# Allwinner_V3s_Dev-board.net
KiCad netlist of a schematic drawn in EAGLE
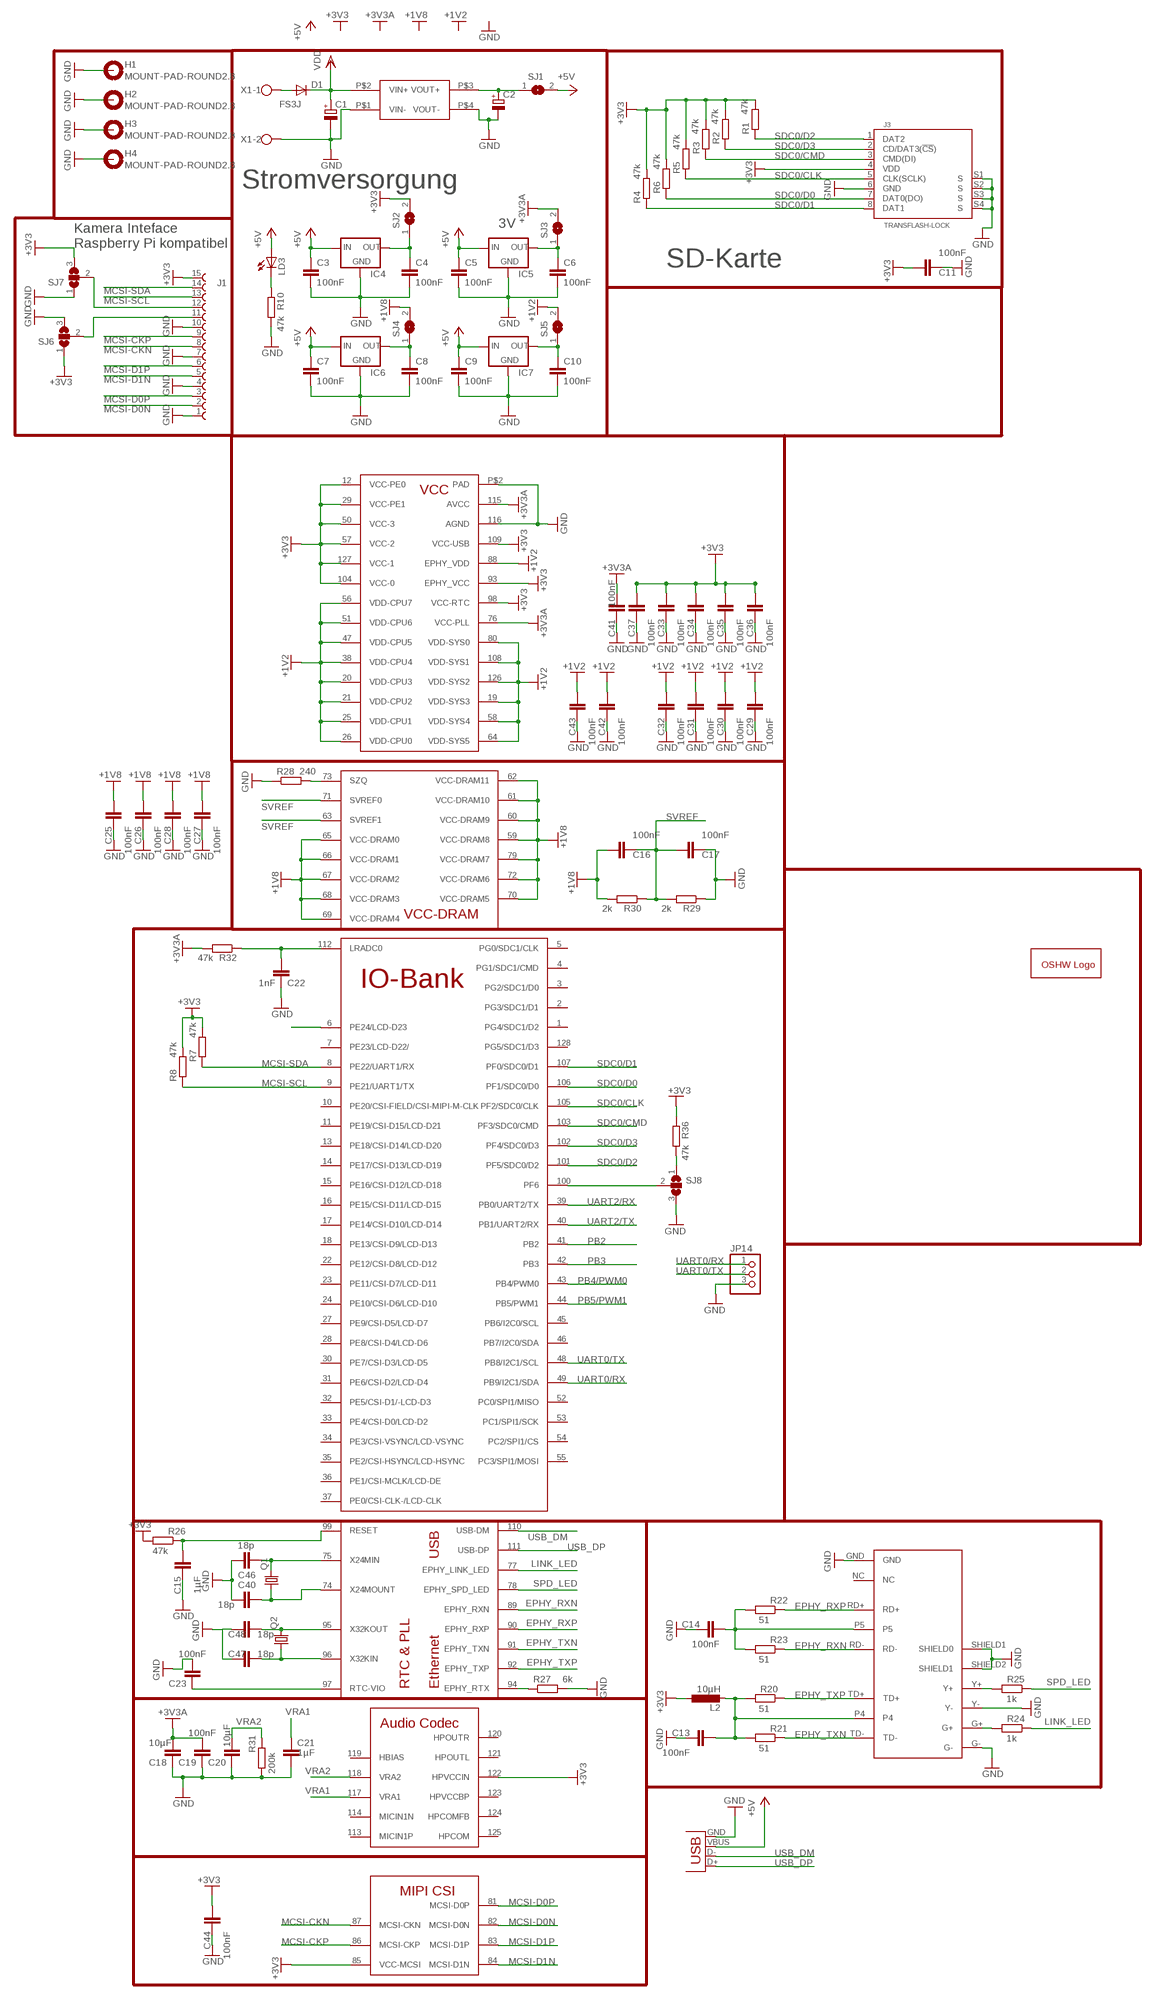
[diagram p0: schematic, sheet 1, part 1 of 2]
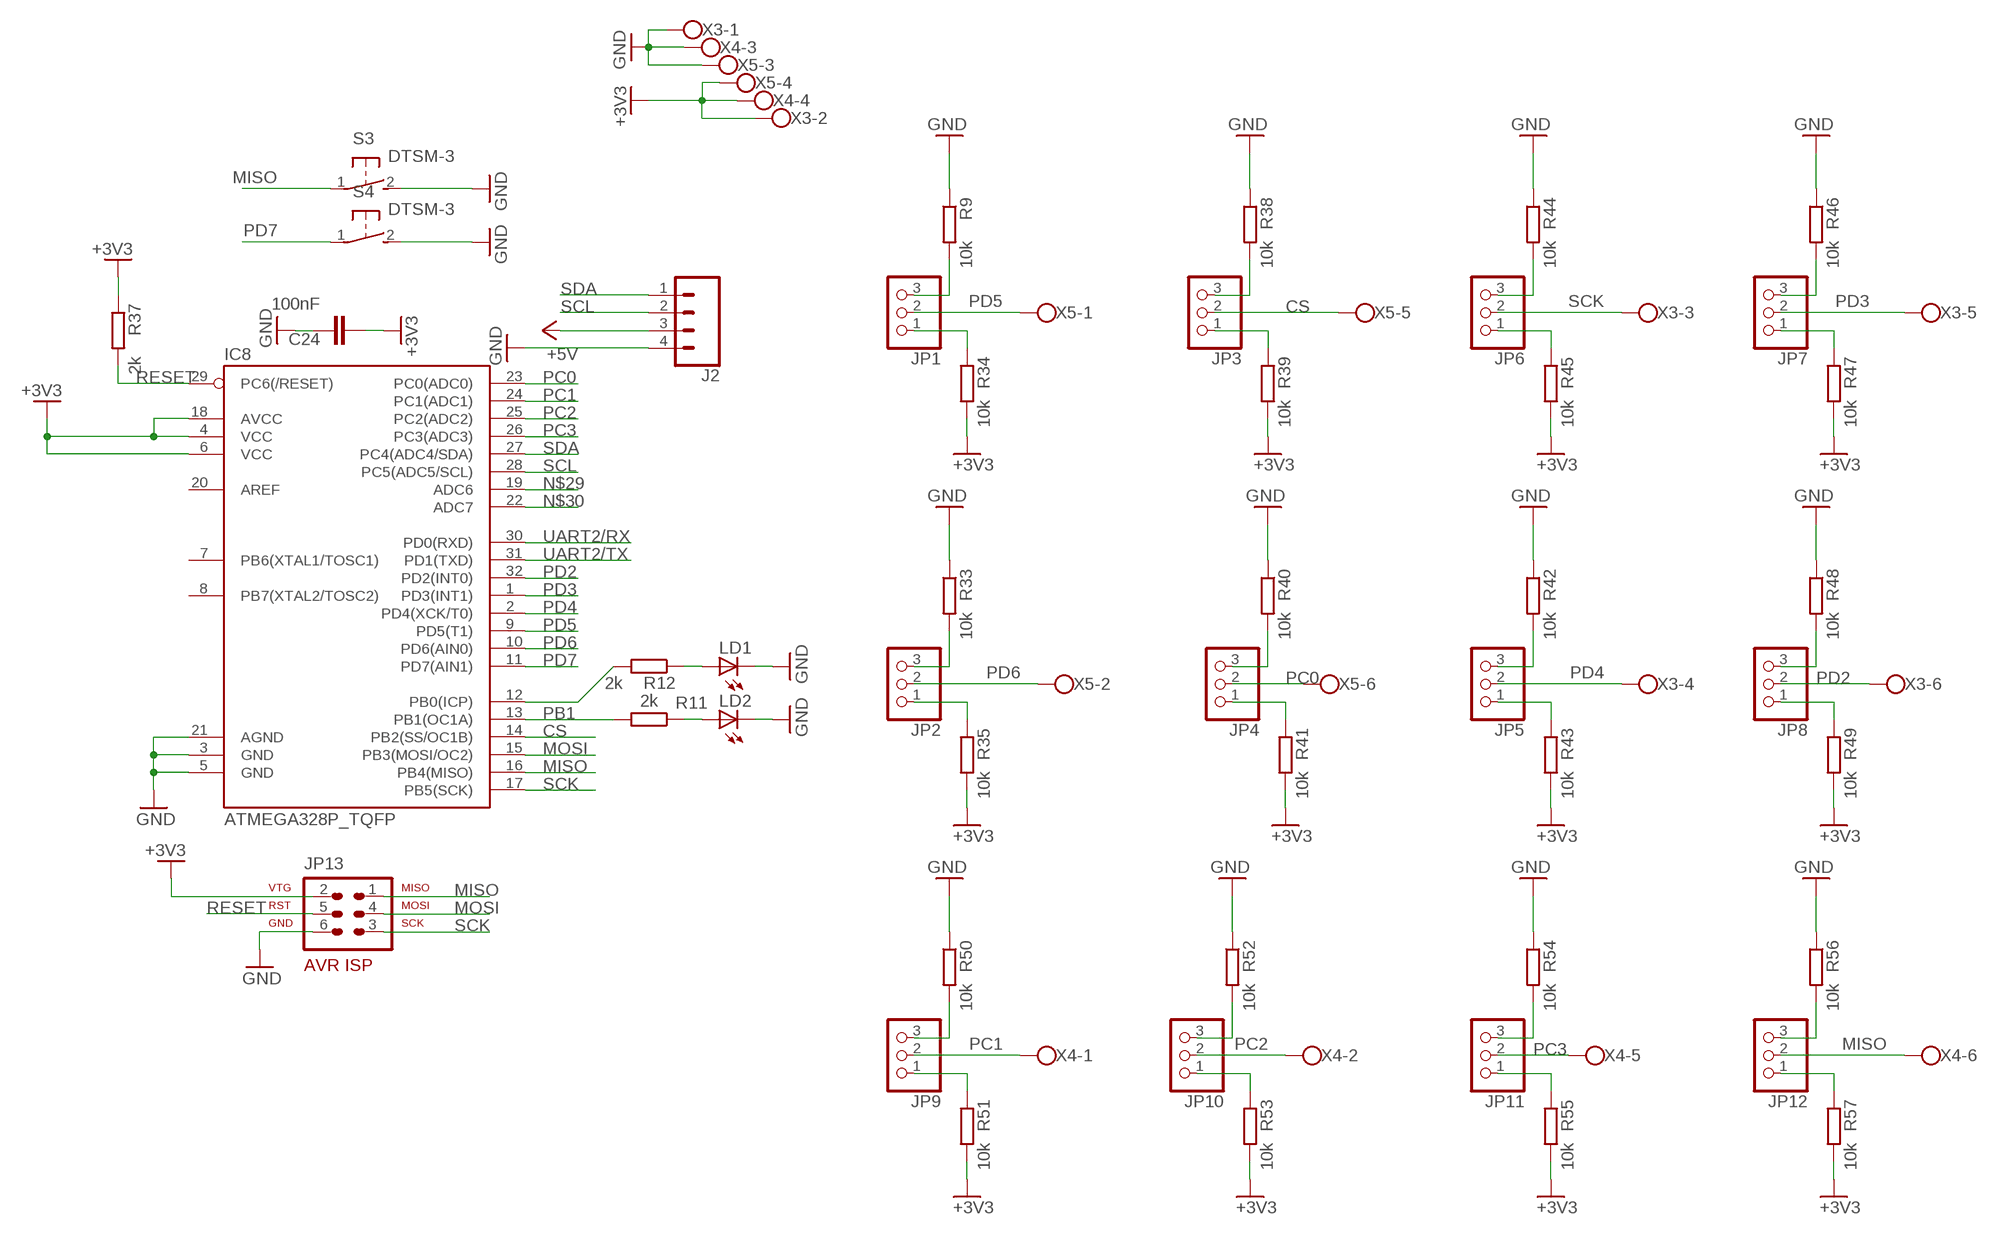
[diagram p1: schematic, sheet 1, part 2 of 2]

(export (version "E")
  (design (tool "Eeschema 10.0.6"))
  (components
    (comp (ref "C1")
      (value "CPOL-EU153CLV-0807")
      (footprint "eagle-import:153CLV-0807")
      (libsource (lib "eagle-import") (part "CPOL-EU153CLV-0807"))
    )
    (comp (ref "C2")
      (value "CPOL-EU153CLV-0807")
      (footprint "eagle-import:153CLV-0807")
      (libsource (lib "eagle-import") (part "CPOL-EU153CLV-0807"))
    )
    (comp (ref "C3")
      (value "100nF")
      (footprint "eagle-import:C0805")
      (libsource (lib "eagle-import") (part "C-EUC0805"))
    )
    (comp (ref "C4")
      (value "100nF")
      (footprint "eagle-import:C0805")
      (libsource (lib "eagle-import") (part "C-EUC0805"))
    )
    (comp (ref "C5")
      (value "100nF")
      (footprint "eagle-import:C0805")
      (libsource (lib "eagle-import") (part "C-EUC0805"))
    )
    (comp (ref "C6")
      (value "100nF")
      (footprint "eagle-import:C0805")
      (libsource (lib "eagle-import") (part "C-EUC0805"))
    )
    (comp (ref "C7")
      (value "100nF")
      (footprint "eagle-import:C0805")
      (libsource (lib "eagle-import") (part "C-EUC0805"))
    )
    (comp (ref "C8")
      (value "100nF")
      (footprint "eagle-import:C0805")
      (libsource (lib "eagle-import") (part "C-EUC0805"))
    )
    (comp (ref "C9")
      (value "100nF")
      (footprint "eagle-import:C0805")
      (libsource (lib "eagle-import") (part "C-EUC0805"))
    )
    (comp (ref "C10")
      (value "100nF")
      (footprint "eagle-import:C0805")
      (libsource (lib "eagle-import") (part "C-EUC0805"))
    )
    (comp (ref "C11")
      (value "100nF")
      (footprint "eagle-import:C0805")
      (libsource (lib "eagle-import") (part "C-EUC0805"))
    )
    (comp (ref "C13")
      (value "100nF")
      (footprint "eagle-import:C0805")
      (libsource (lib "eagle-import") (part "C-EUC0805"))
    )
    (comp (ref "C14")
      (value "100nF")
      (footprint "eagle-import:C0805")
      (libsource (lib "eagle-import") (part "C-EUC0805"))
    )
    (comp (ref "C15")
      (value "1µF")
      (footprint "eagle-import:C0805")
      (libsource (lib "eagle-import") (part "C-EUC0805"))
    )
    (comp (ref "C16")
      (value "100nF")
      (footprint "eagle-import:C0805")
      (libsource (lib "eagle-import") (part "C-EUC0805"))
    )
    (comp (ref "C17")
      (value "100nF")
      (footprint "eagle-import:C0805")
      (libsource (lib "eagle-import") (part "C-EUC0805"))
    )
    (comp (ref "C18")
      (value "10µF")
      (footprint "eagle-import:C0805")
      (libsource (lib "eagle-import") (part "C-EUC0805"))
    )
    (comp (ref "C19")
      (value "100nF")
      (footprint "eagle-import:C0805")
      (libsource (lib "eagle-import") (part "C-EUC0805"))
    )
    (comp (ref "C20")
      (value "10µF")
      (footprint "eagle-import:C0805")
      (libsource (lib "eagle-import") (part "C-EUC0805"))
    )
    (comp (ref "C21")
      (value "1µF")
      (footprint "eagle-import:C0805")
      (libsource (lib "eagle-import") (part "C-EUC0805"))
    )
    (comp (ref "C22")
      (value "1nF")
      (footprint "eagle-import:C0805")
      (libsource (lib "eagle-import") (part "C-EUC0805"))
    )
    (comp (ref "C23")
      (value "100nF")
      (footprint "eagle-import:C0805")
      (libsource (lib "eagle-import") (part "C-EUC0805"))
    )
    (comp (ref "C24")
      (value "100nF")
      (footprint "eagle-import:C0805")
      (libsource (lib "eagle-import") (part "C-EUC0805"))
    )
    (comp (ref "C25")
      (value "100nF")
      (footprint "eagle-import:C0805")
      (libsource (lib "eagle-import") (part "C-EUC0805"))
    )
    (comp (ref "C26")
      (value "100nF")
      (footprint "eagle-import:C0805")
      (libsource (lib "eagle-import") (part "C-EUC0805"))
    )
    (comp (ref "C27")
      (value "100nF")
      (footprint "eagle-import:C0805")
      (libsource (lib "eagle-import") (part "C-EUC0805"))
    )
    (comp (ref "C28")
      (value "100nF")
      (footprint "eagle-import:C0805")
      (libsource (lib "eagle-import") (part "C-EUC0805"))
    )
    (comp (ref "C29")
      (value "100nF")
      (footprint "eagle-import:C0805")
      (libsource (lib "eagle-import") (part "C-EUC0805"))
    )
    (comp (ref "C30")
      (value "100nF")
      (footprint "eagle-import:C0805")
      (libsource (lib "eagle-import") (part "C-EUC0805"))
    )
    (comp (ref "C31")
      (value "100nF")
      (footprint "eagle-import:C0805")
      (libsource (lib "eagle-import") (part "C-EUC0805"))
    )
    (comp (ref "C32")
      (value "100nF")
      (footprint "eagle-import:C0805")
      (libsource (lib "eagle-import") (part "C-EUC0805"))
    )
    (comp (ref "C33")
      (value "100nF")
      (footprint "eagle-import:C0805")
      (libsource (lib "eagle-import") (part "C-EUC0805"))
    )
    (comp (ref "C34")
      (value "100nF")
      (footprint "eagle-import:C0805")
      (libsource (lib "eagle-import") (part "C-EUC0805"))
    )
    (comp (ref "C35")
      (value "100nF")
      (footprint "eagle-import:C0805")
      (libsource (lib "eagle-import") (part "C-EUC0805"))
    )
    (comp (ref "C36")
      (value "100nF")
      (footprint "eagle-import:C0805")
      (libsource (lib "eagle-import") (part "C-EUC0805"))
    )
    (comp (ref "C37")
      (value "100nF")
      (footprint "eagle-import:C0805")
      (libsource (lib "eagle-import") (part "C-EUC0805"))
    )
    (comp (ref "C40")
      (value "18p")
      (footprint "eagle-import:C0805")
      (libsource (lib "eagle-import") (part "C-EUC0805"))
    )
    (comp (ref "C41")
      (value "100nF")
      (footprint "eagle-import:C0805")
      (libsource (lib "eagle-import") (part "C-EUC0805"))
    )
    (comp (ref "C42")
      (value "100nF")
      (footprint "eagle-import:C0805")
      (libsource (lib "eagle-import") (part "C-EUC0805"))
    )
    (comp (ref "C43")
      (value "100nF")
      (footprint "eagle-import:C0805")
      (libsource (lib "eagle-import") (part "C-EUC0805"))
    )
    (comp (ref "C44")
      (value "100nF")
      (footprint "eagle-import:C0805")
      (libsource (lib "eagle-import") (part "C-EUC0805"))
    )
    (comp (ref "C46")
      (value "18p")
      (footprint "eagle-import:C0805")
      (libsource (lib "eagle-import") (part "C-EUC0805"))
    )
    (comp (ref "C47")
      (value "18p")
      (footprint "eagle-import:C0805")
      (libsource (lib "eagle-import") (part "C-EUC0805"))
    )
    (comp (ref "C48")
      (value "18p")
      (footprint "eagle-import:C0805")
      (libsource (lib "eagle-import") (part "C-EUC0805"))
    )
    (comp (ref "D1")
      (value "FS3J")
      (footprint "eagle-import:SMC")
      (libsource (lib "eagle-import") (part "DIODE-SMC"))
    )
    (comp (ref "GOLD_ORB_SM2")
      (value "OSHWLOGOLOGO8MM")
      (footprint "eagle-import:OSHW_8MM")
      (libsource (lib "eagle-import") (part "OSHWLOGOLOGO8MM"))
    )
    (comp (ref "H1")
      (value "MOUNT-PAD-ROUND2.8")
      (footprint "eagle-import:2,8-PAD")
      (libsource (lib "eagle-import") (part "MOUNT-PAD-ROUND2.8"))
    )
    (comp (ref "H2")
      (value "MOUNT-PAD-ROUND2.8")
      (footprint "eagle-import:2,8-PAD")
      (libsource (lib "eagle-import") (part "MOUNT-PAD-ROUND2.8"))
    )
    (comp (ref "H3")
      (value "MOUNT-PAD-ROUND2.8")
      (footprint "eagle-import:2,8-PAD")
      (libsource (lib "eagle-import") (part "MOUNT-PAD-ROUND2.8"))
    )
    (comp (ref "H4")
      (value "MOUNT-PAD-ROUND2.8")
      (footprint "eagle-import:2,8-PAD")
      (libsource (lib "eagle-import") (part "MOUNT-PAD-ROUND2.8"))
    )
    (comp (ref "IC1")
      (value "V3S")
      (footprint "eagle-import:QFP-128")
      (libsource (lib "eagle-import") (part "V3S"))
    )
    (comp (ref "IC4")
      (value "LM1117")
      (footprint "eagle-import:SOT223")
      (libsource (lib "eagle-import") (part "LM1117"))
    )
    (comp (ref "IC5")
      (value "LM1117")
      (footprint "eagle-import:SOT223")
      (libsource (lib "eagle-import") (part "LM1117"))
    )
    (comp (ref "IC6")
      (value "LM1117")
      (footprint "eagle-import:SOT223")
      (libsource (lib "eagle-import") (part "LM1117"))
    )
    (comp (ref "IC7")
      (value "LM1117")
      (footprint "eagle-import:SOT223")
      (libsource (lib "eagle-import") (part "LM1117"))
    )
    (comp (ref "IC8")
      (value "ATMEGA328P_TQFP")
      (footprint "eagle-import:TQFP32-08")
      (libsource (lib "eagle-import") (part "ATMEGA328P_TQFP"))
    )
    (comp (ref "J1")
      (value "68611514122")
      (footprint "eagle-import:68611514122")
      (libsource (lib "eagle-import") (part "68611514122"))
    )
    (comp (ref "J2")
      (value "CONN_04SMD_LONG")
      (footprint "eagle-import:1X04_SMD_LONG")
      (libsource (lib "eagle-import") (part "CONN_04SMD_LONG"))
    )
    (comp (ref "J3")
      (value "TRANSFLASH-LOCK")
      (footprint "eagle-import:TRANSFLASH-LOCK-SOCK")
      (libsource (lib "eagle-import") (part "TRANSFLASH-LOCK"))
    )
    (comp (ref "JP1")
      (value "PINHD-1X3")
      (footprint "eagle-import:1X03")
      (libsource (lib "eagle-import") (part "PINHD-1X3"))
    )
    (comp (ref "JP2")
      (value "PINHD-1X3")
      (footprint "eagle-import:1X03")
      (libsource (lib "eagle-import") (part "PINHD-1X3"))
    )
    (comp (ref "JP3")
      (value "PINHD-1X3")
      (footprint "eagle-import:1X03")
      (libsource (lib "eagle-import") (part "PINHD-1X3"))
    )
    (comp (ref "JP4")
      (value "PINHD-1X3")
      (footprint "eagle-import:1X03")
      (libsource (lib "eagle-import") (part "PINHD-1X3"))
    )
    (comp (ref "JP5")
      (value "PINHD-1X3")
      (footprint "eagle-import:1X03")
      (libsource (lib "eagle-import") (part "PINHD-1X3"))
    )
    (comp (ref "JP6")
      (value "PINHD-1X3")
      (footprint "eagle-import:1X03")
      (libsource (lib "eagle-import") (part "PINHD-1X3"))
    )
    (comp (ref "JP7")
      (value "PINHD-1X3")
      (footprint "eagle-import:1X03")
      (libsource (lib "eagle-import") (part "PINHD-1X3"))
    )
    (comp (ref "JP8")
      (value "PINHD-1X3")
      (footprint "eagle-import:1X03")
      (libsource (lib "eagle-import") (part "PINHD-1X3"))
    )
    (comp (ref "JP9")
      (value "PINHD-1X3")
      (footprint "eagle-import:1X03")
      (libsource (lib "eagle-import") (part "PINHD-1X3"))
    )
    (comp (ref "JP10")
      (value "PINHD-1X3")
      (footprint "eagle-import:1X03")
      (libsource (lib "eagle-import") (part "PINHD-1X3"))
    )
    (comp (ref "JP11")
      (value "PINHD-1X3")
      (footprint "eagle-import:1X03")
      (libsource (lib "eagle-import") (part "PINHD-1X3"))
    )
    (comp (ref "JP12")
      (value "PINHD-1X3")
      (footprint "eagle-import:1X03")
      (libsource (lib "eagle-import") (part "PINHD-1X3"))
    )
    (comp (ref "JP13")
      (value "AVR-ISP-6")
      (footprint "eagle-import:AVR-ISP-6")
      (libsource (lib "eagle-import") (part "AVR-ISP-6"))
    )
    (comp (ref "JP14")
      (value "PINHD-1X3")
      (footprint "eagle-import:1X03")
      (libsource (lib "eagle-import") (part "PINHD-1X3"))
    )
    (comp (ref "L2")
      (value "10µH")
      (footprint "eagle-import:L0805")
      (libsource (lib "eagle-import") (part "L-EUL0805"))
    )
    (comp (ref "LD1")
      (value "LEDSMT1206")
      (footprint "eagle-import:1206")
      (libsource (lib "eagle-import") (part "LEDSMT1206"))
    )
    (comp (ref "LD2")
      (value "LEDSMT1206")
      (footprint "eagle-import:1206")
      (libsource (lib "eagle-import") (part "LEDSMT1206"))
    )
    (comp (ref "LD3")
      (value "LEDSMT1206")
      (footprint "eagle-import:1206")
      (libsource (lib "eagle-import") (part "LEDSMT1206"))
    )
    (comp (ref "M1")
      (value "MP1584-MINI")
      (footprint "eagle-import:MINI-DC-BRICK")
      (libsource (lib "eagle-import") (part "MP1584-MINI"))
    )
    (comp (ref "Q1")
      (value "CRYSTALHC49S")
      (footprint "eagle-import:HC49_S")
      (libsource (lib "eagle-import") (part "CRYSTALHC49S"))
    )
    (comp (ref "Q2")
      (value "CRYSTALTC26H")
      (footprint "eagle-import:TC26H")
      (libsource (lib "eagle-import") (part "CRYSTALTC26H"))
    )
    (comp (ref "R1")
      (value "47k")
      (footprint "eagle-import:R0805")
      (libsource (lib "eagle-import") (part "R-EU_R0805"))
    )
    (comp (ref "R2")
      (value "47k")
      (footprint "eagle-import:R0805")
      (libsource (lib "eagle-import") (part "R-EU_R0805"))
    )
    (comp (ref "R3")
      (value "47k")
      (footprint "eagle-import:R0805")
      (libsource (lib "eagle-import") (part "R-EU_R0805"))
    )
    (comp (ref "R4")
      (value "47k")
      (footprint "eagle-import:R0805")
      (libsource (lib "eagle-import") (part "R-EU_R0805"))
    )
    (comp (ref "R5")
      (value "47k")
      (footprint "eagle-import:R0805")
      (libsource (lib "eagle-import") (part "R-EU_R0805"))
    )
    (comp (ref "R6")
      (value "47k")
      (footprint "eagle-import:R0805")
      (libsource (lib "eagle-import") (part "R-EU_R0805"))
    )
    (comp (ref "R7")
      (value "47k")
      (footprint "eagle-import:R0805")
      (libsource (lib "eagle-import") (part "R-EU_R0805"))
    )
    (comp (ref "R8")
      (value "47k")
      (footprint "eagle-import:R0805")
      (libsource (lib "eagle-import") (part "R-EU_R0805"))
    )
    (comp (ref "R9")
      (value "10k")
      (footprint "eagle-import:R0805")
      (libsource (lib "eagle-import") (part "R-EU_R0805"))
    )
    (comp (ref "R10")
      (value "47k")
      (footprint "eagle-import:R0805")
      (libsource (lib "eagle-import") (part "R-EU_R0805"))
    )
    (comp (ref "R11")
      (value "2k")
      (footprint "eagle-import:R0805")
      (libsource (lib "eagle-import") (part "R-EU_R0805"))
    )
    (comp (ref "R12")
      (value "2k")
      (footprint "eagle-import:R0805")
      (libsource (lib "eagle-import") (part "R-EU_R0805"))
    )
    (comp (ref "R20")
      (value "51")
      (footprint "eagle-import:R0805")
      (libsource (lib "eagle-import") (part "R-EU_R0805"))
    )
    (comp (ref "R21")
      (value "51")
      (footprint "eagle-import:R0805")
      (libsource (lib "eagle-import") (part "R-EU_R0805"))
    )
    (comp (ref "R22")
      (value "51")
      (footprint "eagle-import:R0805")
      (libsource (lib "eagle-import") (part "R-EU_R0805"))
    )
    (comp (ref "R23")
      (value "51")
      (footprint "eagle-import:R0805")
      (libsource (lib "eagle-import") (part "R-EU_R0805"))
    )
    (comp (ref "R24")
      (value "1k")
      (footprint "eagle-import:R0805")
      (libsource (lib "eagle-import") (part "R-EU_R0805"))
    )
    (comp (ref "R25")
      (value "1k")
      (footprint "eagle-import:R0805")
      (libsource (lib "eagle-import") (part "R-EU_R0805"))
    )
    (comp (ref "R26")
      (value "47k")
      (footprint "eagle-import:R0805")
      (libsource (lib "eagle-import") (part "R-EU_R0805"))
    )
    (comp (ref "R27")
      (value "6k")
      (footprint "eagle-import:R0805")
      (libsource (lib "eagle-import") (part "R-EU_R0805"))
    )
    (comp (ref "R28")
      (value "240")
      (footprint "eagle-import:R0805")
      (libsource (lib "eagle-import") (part "R-EU_R0805"))
    )
    (comp (ref "R29")
      (value "2k")
      (footprint "eagle-import:R0805")
      (libsource (lib "eagle-import") (part "R-EU_R0805"))
    )
    (comp (ref "R30")
      (value "2k")
      (footprint "eagle-import:R0805")
      (libsource (lib "eagle-import") (part "R-EU_R0805"))
    )
    (comp (ref "R31")
      (value "200k")
      (footprint "eagle-import:R0805")
      (libsource (lib "eagle-import") (part "R-EU_R0805"))
    )
    (comp (ref "R32")
      (value "47k")
      (footprint "eagle-import:R0805")
      (libsource (lib "eagle-import") (part "R-EU_R0805"))
    )
    (comp (ref "R33")
      (value "10k")
      (footprint "eagle-import:R0805")
      (libsource (lib "eagle-import") (part "R-EU_R0805"))
    )
    (comp (ref "R34")
      (value "10k")
      (footprint "eagle-import:R0805")
      (libsource (lib "eagle-import") (part "R-EU_R0805"))
    )
    (comp (ref "R35")
      (value "10k")
      (footprint "eagle-import:R0805")
      (libsource (lib "eagle-import") (part "R-EU_R0805"))
    )
    (comp (ref "R36")
      (value "47k")
      (footprint "eagle-import:R0805")
      (libsource (lib "eagle-import") (part "R-EU_R0805"))
    )
    (comp (ref "R37")
      (value "2k")
      (footprint "eagle-import:R0805")
      (libsource (lib "eagle-import") (part "R-EU_R0805"))
    )
    (comp (ref "R38")
      (value "10k")
      (footprint "eagle-import:R0805")
      (libsource (lib "eagle-import") (part "R-EU_R0805"))
    )
    (comp (ref "R39")
      (value "10k")
      (footprint "eagle-import:R0805")
      (libsource (lib "eagle-import") (part "R-EU_R0805"))
    )
    (comp (ref "R40")
      (value "10k")
      (footprint "eagle-import:R0805")
      (libsource (lib "eagle-import") (part "R-EU_R0805"))
    )
    (comp (ref "R41")
      (value "10k")
      (footprint "eagle-import:R0805")
      (libsource (lib "eagle-import") (part "R-EU_R0805"))
    )
    (comp (ref "R42")
      (value "10k")
      (footprint "eagle-import:R0805")
      (libsource (lib "eagle-import") (part "R-EU_R0805"))
    )
    (comp (ref "R43")
      (value "10k")
      (footprint "eagle-import:R0805")
      (libsource (lib "eagle-import") (part "R-EU_R0805"))
    )
    (comp (ref "R44")
      (value "10k")
      (footprint "eagle-import:R0805")
      (libsource (lib "eagle-import") (part "R-EU_R0805"))
    )
    (comp (ref "R45")
      (value "10k")
      (footprint "eagle-import:R0805")
      (libsource (lib "eagle-import") (part "R-EU_R0805"))
    )
    (comp (ref "R46")
      (value "10k")
      (footprint "eagle-import:R0805")
      (libsource (lib "eagle-import") (part "R-EU_R0805"))
    )
    (comp (ref "R47")
      (value "10k")
      (footprint "eagle-import:R0805")
      (libsource (lib "eagle-import") (part "R-EU_R0805"))
    )
    (comp (ref "R48")
      (value "10k")
      (footprint "eagle-import:R0805")
      (libsource (lib "eagle-import") (part "R-EU_R0805"))
    )
    (comp (ref "R49")
      (value "10k")
      (footprint "eagle-import:R0805")
      (libsource (lib "eagle-import") (part "R-EU_R0805"))
    )
    (comp (ref "R50")
      (value "10k")
      (footprint "eagle-import:R0805")
      (libsource (lib "eagle-import") (part "R-EU_R0805"))
    )
    (comp (ref "R51")
      (value "10k")
      (footprint "eagle-import:R0805")
      (libsource (lib "eagle-import") (part "R-EU_R0805"))
    )
    (comp (ref "R52")
      (value "10k")
      (footprint "eagle-import:R0805")
      (libsource (lib "eagle-import") (part "R-EU_R0805"))
    )
    (comp (ref "R53")
      (value "10k")
      (footprint "eagle-import:R0805")
      (libsource (lib "eagle-import") (part "R-EU_R0805"))
    )
    (comp (ref "R54")
      (value "10k")
      (footprint "eagle-import:R0805")
      (libsource (lib "eagle-import") (part "R-EU_R0805"))
    )
    (comp (ref "R55")
      (value "10k")
      (footprint "eagle-import:R0805")
      (libsource (lib "eagle-import") (part "R-EU_R0805"))
    )
    (comp (ref "R56")
      (value "10k")
      (footprint "eagle-import:R0805")
      (libsource (lib "eagle-import") (part "R-EU_R0805"))
    )
    (comp (ref "R57")
      (value "10k")
      (footprint "eagle-import:R0805")
      (libsource (lib "eagle-import") (part "R-EU_R0805"))
    )
    (comp (ref "S3")
      (value "DTSM-3")
      (footprint "eagle-import:DTSM-3")
      (libsource (lib "eagle-import") (part "DTSM-3"))
    )
    (comp (ref "S4")
      (value "DTSM-3")
      (footprint "eagle-import:DTSM-3")
      (libsource (lib "eagle-import") (part "DTSM-3"))
    )
    (comp (ref "SJ1") (value "SJ") (footprint "eagle-import:SJ") (libsource (lib "eagle-import") (part "SJ")))
    (comp (ref "SJ2") (value "SJ") (footprint "eagle-import:SJ") (libsource (lib "eagle-import") (part "SJ")))
    (comp (ref "SJ3") (value "SJ") (footprint "eagle-import:SJ") (libsource (lib "eagle-import") (part "SJ")))
    (comp (ref "SJ4") (value "SJ") (footprint "eagle-import:SJ") (libsource (lib "eagle-import") (part "SJ")))
    (comp (ref "SJ5") (value "SJ") (footprint "eagle-import:SJ") (libsource (lib "eagle-import") (part "SJ")))
    (comp (ref "SJ6")
      (value "SJ2W")
      (footprint "eagle-import:SJ_2")
      (libsource (lib "eagle-import") (part "SJ2W"))
    )
    (comp (ref "SJ7")
      (value "SJ2W")
      (footprint "eagle-import:SJ_2")
      (libsource (lib "eagle-import") (part "SJ2W"))
    )
    (comp (ref "SJ8")
      (value "SJ2W")
      (footprint "eagle-import:SJ_2")
      (libsource (lib "eagle-import") (part "SJ2W"))
    )
    (comp (ref "U$3")
      (value "HR911105A")
      (footprint "eagle-import:RJ45")
      (libsource (lib "eagle-import") (part "HR911105A"))
    )
    (comp (ref "X1")
      (value "W237-102")
      (footprint "eagle-import:W237-102")
      (libsource (lib "eagle-import") (part "W237-102"))
    )
    (comp (ref "X2")
      (value "USB-A-H")
      (footprint "eagle-import:USB-A-H")
      (libsource (lib "eagle-import") (part "USB-A-H"))
    )
    (comp (ref "X3")
      (value "W237-6")
      (footprint "eagle-import:W237-6")
      (libsource (lib "eagle-import") (part "W237-6"))
    )
    (comp (ref "X4")
      (value "W237-6")
      (footprint "eagle-import:W237-6")
      (libsource (lib "eagle-import") (part "W237-6"))
    )
    (comp (ref "X5")
      (value "W237-6")
      (footprint "eagle-import:W237-6")
      (libsource (lib "eagle-import") (part "W237-6"))
    )
  )
  (nets
    (net (code "1") (name "+1V2") (class "Default")
      (node (ref "C29") (pin "1") (pinfunction "1_1") (pintype "passive"))
      (node (ref "C30") (pin "1") (pinfunction "1_1") (pintype "passive"))
      (node (ref "C31") (pin "1") (pinfunction "1_1") (pintype "passive"))
      (node (ref "C32") (pin "1") (pinfunction "1_1") (pintype "passive"))
      (node (ref "C42") (pin "1") (pinfunction "1_1") (pintype "passive"))
      (node (ref "C43") (pin "1") (pinfunction "1_1") (pintype "passive"))
      (node (ref "IC1") (pin "108") (pinfunction "VDD-SYS1_108") (pintype "bidirectional"))
      (node (ref "IC1") (pin "126") (pinfunction "VDD-SYS2_126") (pintype "bidirectional"))
      (node (ref "IC1") (pin "19") (pinfunction "VDD-SYS3_19") (pintype "bidirectional"))
      (node (ref "IC1") (pin "20") (pinfunction "VDD-CPU3_20") (pintype "bidirectional"))
      (node (ref "IC1") (pin "21") (pinfunction "VDD-CPU2_21") (pintype "bidirectional"))
      (node (ref "IC1") (pin "25") (pinfunction "VDD-CPU1_25") (pintype "bidirectional"))
      (node (ref "IC1") (pin "26") (pinfunction "VDD-CPU0_26") (pintype "bidirectional"))
      (node (ref "IC1") (pin "38") (pinfunction "VDD-CPU4_38") (pintype "bidirectional"))
      (node (ref "IC1") (pin "47") (pinfunction "VDD-CPU5_47") (pintype "bidirectional"))
      (node (ref "IC1") (pin "51") (pinfunction "VDD-CPU6_51") (pintype "bidirectional"))
      (node (ref "IC1") (pin "56") (pinfunction "VDD-CPU7_56") (pintype "bidirectional"))
      (node (ref "IC1") (pin "58") (pinfunction "VDD-SYS4_58") (pintype "bidirectional"))
      (node (ref "IC1") (pin "64") (pinfunction "VDD-SYS5_64") (pintype "bidirectional"))
      (node (ref "IC1") (pin "80") (pinfunction "VDD-SYS0_80") (pintype "bidirectional"))
      (node (ref "IC1") (pin "88") (pinfunction "EPHY_VDD_88") (pintype "bidirectional"))
      (node (ref "SJ5") (pin "2") (pinfunction "2_2") (pintype "passive"))
    )
    (net (code "2") (name "+1V8") (class "Default")
      (node (ref "C16") (pin "1") (pinfunction "1_1") (pintype "passive"))
      (node (ref "C25") (pin "1") (pinfunction "1_1") (pintype "passive"))
      (node (ref "C26") (pin "1") (pinfunction "1_1") (pintype "passive"))
      (node (ref "C27") (pin "1") (pinfunction "1_1") (pintype "passive"))
      (node (ref "C28") (pin "1") (pinfunction "1_1") (pintype "passive"))
      (node (ref "IC1") (pin "59") (pinfunction "VCC-DRAM8_59") (pintype "bidirectional"))
      (node (ref "IC1") (pin "60") (pinfunction "VCC-DRAM9_60") (pintype "bidirectional"))
      (node (ref "IC1") (pin "61") (pinfunction "VCC-DRAM10_61") (pintype "bidirectional"))
      (node (ref "IC1") (pin "62") (pinfunction "VCC-DRAM11_62") (pintype "bidirectional"))
      (node (ref "IC1") (pin "65") (pinfunction "VCC-DRAM0_65") (pintype "bidirectional"))
      (node (ref "IC1") (pin "66") (pinfunction "VCC-DRAM1_66") (pintype "bidirectional"))
      (node (ref "IC1") (pin "67") (pinfunction "VCC-DRAM2_67") (pintype "bidirectional"))
      (node (ref "IC1") (pin "68") (pinfunction "VCC-DRAM3_68") (pintype "bidirectional"))
      (node (ref "IC1") (pin "69") (pinfunction "VCC-DRAM4_69") (pintype "bidirectional"))
      (node (ref "IC1") (pin "70") (pinfunction "VCC-DRAM5_70") (pintype "bidirectional"))
      (node (ref "IC1") (pin "72") (pinfunction "VCC-DRAM6_72") (pintype "bidirectional"))
      (node (ref "IC1") (pin "79") (pinfunction "VCC-DRAM7_79") (pintype "bidirectional"))
      (node (ref "R30") (pin "2") (pinfunction "2_2") (pintype "passive"))
      (node (ref "SJ4") (pin "2") (pinfunction "2_2") (pintype "passive"))
    )
    (net (code "3") (name "+3V3") (class "Default")
      (node (ref "C11") (pin "1") (pinfunction "1_1") (pintype "passive"))
      (node (ref "C24") (pin "1") (pinfunction "1_1") (pintype "passive"))
      (node (ref "C33") (pin "1") (pinfunction "1_1") (pintype "passive"))
      (node (ref "C34") (pin "1") (pinfunction "1_1") (pintype "passive"))
      (node (ref "C35") (pin "1") (pinfunction "1_1") (pintype "passive"))
      (node (ref "C36") (pin "1") (pinfunction "1_1") (pintype "passive"))
      (node (ref "C37") (pin "1") (pinfunction "1_1") (pintype "passive"))
      (node (ref "C44") (pin "1") (pinfunction "1_1") (pintype "passive"))
      (node (ref "IC1") (pin "104") (pinfunction "VCC-0_104") (pintype "bidirectional"))
      (node (ref "IC1") (pin "109") (pinfunction "VCC-USB_109") (pintype "bidirectional"))
      (node (ref "IC1") (pin "12") (pinfunction "VCC-PE0_12") (pintype "bidirectional"))
      (node (ref "IC1") (pin "122") (pinfunction "HPVCCIN_122") (pintype "bidirectional"))
      (node (ref "IC1") (pin "127") (pinfunction "VCC-1_127") (pintype "bidirectional"))
      (node (ref "IC1") (pin "29") (pinfunction "VCC-PE1_29") (pintype "bidirectional"))
      (node (ref "IC1") (pin "50") (pinfunction "VCC-3_50") (pintype "bidirectional"))
      (node (ref "IC1") (pin "57") (pinfunction "VCC-2_57") (pintype "bidirectional"))
      (node (ref "IC1") (pin "85") (pinfunction "VCC-MCSI_85") (pintype "bidirectional"))
      (node (ref "IC1") (pin "93") (pinfunction "EPHY_VCC_93") (pintype "bidirectional"))
      (node (ref "IC1") (pin "98") (pinfunction "VCC-RTC_98") (pintype "bidirectional"))
      (node (ref "IC8") (pin "18") (pinfunction "AVCC_18") (pintype "bidirectional"))
      (node (ref "IC8") (pin "4") (pinfunction "VCC_4") (pintype "bidirectional"))
      (node (ref "IC8") (pin "6") (pinfunction "VCC_6") (pintype "bidirectional"))
      (node (ref "J1") (pin "15") (pinfunction "1_15") (pintype "passive"))
      (node (ref "J3") (pin "4") (pinfunction "VDD_4") (pintype "power_in"))
      (node (ref "JP13") (pin "2") (pinfunction "2_2") (pintype "passive"))
      (node (ref "L2") (pin "1") (pinfunction "1_1") (pintype "passive"))
      (node (ref "R1") (pin "2") (pinfunction "2_2") (pintype "passive"))
      (node (ref "R2") (pin "2") (pinfunction "2_2") (pintype "passive"))
      (node (ref "R26") (pin "2") (pinfunction "2_2") (pintype "passive"))
      (node (ref "R3") (pin "2") (pinfunction "2_2") (pintype "passive"))
      (node (ref "R34") (pin "2") (pinfunction "2_2") (pintype "passive"))
      (node (ref "R35") (pin "2") (pinfunction "2_2") (pintype "passive"))
      (node (ref "R36") (pin "1") (pinfunction "1_1") (pintype "passive"))
      (node (ref "R37") (pin "1") (pinfunction "1_1") (pintype "passive"))
      (node (ref "R39") (pin "2") (pinfunction "2_2") (pintype "passive"))
      (node (ref "R4") (pin "2") (pinfunction "2_2") (pintype "passive"))
      (node (ref "R41") (pin "2") (pinfunction "2_2") (pintype "passive"))
      (node (ref "R43") (pin "2") (pinfunction "2_2") (pintype "passive"))
      (node (ref "R45") (pin "2") (pinfunction "2_2") (pintype "passive"))
      (node (ref "R47") (pin "2") (pinfunction "2_2") (pintype "passive"))
      (node (ref "R49") (pin "2") (pinfunction "2_2") (pintype "passive"))
      (node (ref "R5") (pin "2") (pinfunction "2_2") (pintype "passive"))
      (node (ref "R51") (pin "2") (pinfunction "2_2") (pintype "passive"))
      (node (ref "R53") (pin "2") (pinfunction "2_2") (pintype "passive"))
      (node (ref "R55") (pin "2") (pinfunction "2_2") (pintype "passive"))
      (node (ref "R57") (pin "2") (pinfunction "2_2") (pintype "passive"))
      (node (ref "R6") (pin "2") (pinfunction "2_2") (pintype "passive"))
      (node (ref "R7") (pin "2") (pinfunction "2_2") (pintype "passive"))
      (node (ref "R8") (pin "2") (pinfunction "2_2") (pintype "passive"))
      (node (ref "SJ2") (pin "2") (pinfunction "2_2") (pintype "passive"))
      (node (ref "SJ6") (pin "1") (pinfunction "1_1") (pintype "passive"))
      (node (ref "SJ7") (pin "3") (pinfunction "3_3") (pintype "passive"))
      (node (ref "X3") (pin "2") (pinfunction "KL_2") (pintype "passive"))
      (node (ref "X4") (pin "4") (pinfunction "KL_4") (pintype "passive"))
      (node (ref "X5") (pin "4") (pinfunction "KL_4") (pintype "passive"))
    )
    (net (code "4") (name "+3V3A") (class "Default")
      (node (ref "C18") (pin "1") (pinfunction "1_1") (pintype "passive"))
      (node (ref "C19") (pin "1") (pinfunction "1_1") (pintype "passive"))
      (node (ref "C41") (pin "1") (pinfunction "1_1") (pintype "passive"))
      (node (ref "IC1") (pin "115") (pinfunction "AVCC_115") (pintype "bidirectional"))
      (node (ref "IC1") (pin "76") (pinfunction "VCC-PLL_76") (pintype "bidirectional"))
      (node (ref "R32") (pin "2") (pinfunction "2_2") (pintype "passive"))
      (node (ref "SJ3") (pin "2") (pinfunction "2_2") (pintype "passive"))
    )
    (net (code "5") (name "+5V") (class "Default")
      (node (ref "C3") (pin "1") (pinfunction "1_1") (pintype "passive"))
      (node (ref "C5") (pin "1") (pinfunction "1_1") (pintype "passive"))
      (node (ref "C7") (pin "1") (pinfunction "1_1") (pintype "passive"))
      (node (ref "C9") (pin "1") (pinfunction "1_1") (pintype "passive"))
      (node (ref "IC4") (pin "3") (pinfunction "IN_3") (pintype "input"))
      (node (ref "IC5") (pin "3") (pinfunction "IN_3") (pintype "input"))
      (node (ref "IC6") (pin "3") (pinfunction "IN_3") (pintype "input"))
      (node (ref "IC7") (pin "3") (pinfunction "IN_3") (pintype "input"))
      (node (ref "J2") (pin "3") (pinfunction "3_3") (pintype "passive"))
      (node (ref "LD3") (pin "A") (pinfunction "A_A") (pintype "passive"))
      (node (ref "SJ1") (pin "2") (pinfunction "2_2") (pintype "passive"))
      (node (ref "X2") (pin "VBUS") (pinfunction "VBUS_VBUS") (pintype "bidirectional"))
    )
    (net (code "6") (name "/CS") (class "Default")
      (node (ref "IC8") (pin "14") (pinfunction "PB2(SS/OC1B)_14") (pintype "bidirectional"))
      (node (ref "JP3") (pin "2") (pinfunction "2_2") (pintype "passive"))
      (node (ref "X5") (pin "5") (pinfunction "KL_5") (pintype "passive"))
    )
    (net (code "7") (name "/EPHY_RXN") (class "Default")
      (node (ref "IC1") (pin "89") (pinfunction "EPHY_RXN_89") (pintype "bidirectional"))
      (node (ref "R23") (pin "1") (pinfunction "1_1") (pintype "passive"))
      (node (ref "U$3") (pin "RD-") (pinfunction "RD-_RD-") (pintype "bidirectional"))
    )
    (net (code "8") (name "/EPHY_RXP") (class "Default")
      (node (ref "IC1") (pin "90") (pinfunction "EPHY_RXP_90") (pintype "bidirectional"))
      (node (ref "R22") (pin "1") (pinfunction "1_1") (pintype "passive"))
      (node (ref "U$3") (pin "RD+") (pinfunction "RD+_RD+") (pintype "bidirectional"))
    )
    (net (code "9") (name "/EPHY_TXN") (class "Default")
      (node (ref "IC1") (pin "91") (pinfunction "EPHY_TXN_91") (pintype "bidirectional"))
      (node (ref "R21") (pin "1") (pinfunction "1_1") (pintype "passive"))
      (node (ref "U$3") (pin "TD-") (pinfunction "TD-_TD-") (pintype "bidirectional"))
    )
    (net (code "10") (name "/EPHY_TXP") (class "Default")
      (node (ref "IC1") (pin "92") (pinfunction "EPHY_TXP_92") (pintype "bidirectional"))
      (node (ref "R20") (pin "1") (pinfunction "1_1") (pintype "passive"))
      (node (ref "U$3") (pin "TD+") (pinfunction "TD+_TD+") (pintype "bidirectional"))
    )
    (net (code "11") (name "/LINK_LED") (class "Default")
      (node (ref "IC1") (pin "77") (pinfunction "EPHY_LINK_LED_77") (pintype "bidirectional"))
      (node (ref "R24") (pin "1") (pinfunction "1_1") (pintype "passive"))
    )
    (net (code "12") (name "/MCSI-CKN") (class "Default")
      (node (ref "IC1") (pin "87") (pinfunction "MCSI-CKN_87") (pintype "bidirectional"))
      (node (ref "J1") (pin "8") (pinfunction "8_8") (pintype "passive"))
    )
    (net (code "13") (name "/MCSI-CKP") (class "Default")
      (node (ref "IC1") (pin "86") (pinfunction "MCSI-CKP_86") (pintype "bidirectional"))
      (node (ref "J1") (pin "9") (pinfunction "7_9") (pintype "passive"))
    )
    (net (code "14") (name "/MCSI-D0N") (class "Default")
      (node (ref "IC1") (pin "82") (pinfunction "MCSI-D0N_82") (pintype "bidirectional"))
      (node (ref "J1") (pin "2") (pinfunction "14_2") (pintype "passive"))
    )
    (net (code "15") (name "/MCSI-D0P") (class "Default")
      (node (ref "IC1") (pin "81") (pinfunction "MCSI-D0P_81") (pintype "bidirectional"))
      (node (ref "J1") (pin "3") (pinfunction "13_3") (pintype "passive"))
    )
    (net (code "16") (name "/MCSI-D1N") (class "Default")
      (node (ref "IC1") (pin "84") (pinfunction "MCSI-D1N_84") (pintype "bidirectional"))
      (node (ref "J1") (pin "5") (pinfunction "11_5") (pintype "passive"))
    )
    (net (code "17") (name "/MCSI-D1P") (class "Default")
      (node (ref "IC1") (pin "83") (pinfunction "MCSI-D1P_83") (pintype "bidirectional"))
      (node (ref "J1") (pin "6") (pinfunction "10_6") (pintype "passive"))
    )
    (net (code "18") (name "/MCSI-SCL") (class "Default")
      (node (ref "IC1") (pin "9") (pinfunction "PE21/UART1/TX_9") (pintype "bidirectional"))
      (node (ref "J1") (pin "13") (pinfunction "3_13") (pintype "passive"))
      (node (ref "R8") (pin "1") (pinfunction "1_1") (pintype "passive"))
    )
    (net (code "19") (name "/MCSI-SDA") (class "Default")
      (node (ref "IC1") (pin "8") (pinfunction "PE22/UART1/RX_8") (pintype "bidirectional"))
      (node (ref "J1") (pin "14") (pinfunction "2_14") (pintype "passive"))
      (node (ref "R7") (pin "1") (pinfunction "1_1") (pintype "passive"))
    )
    (net (code "20") (name "/MISO") (class "Default")
      (node (ref "IC8") (pin "16") (pinfunction "PB4(MISO)_16") (pintype "bidirectional"))
      (node (ref "JP12") (pin "2") (pinfunction "2_2") (pintype "passive"))
      (node (ref "JP13") (pin "1") (pinfunction "1_1") (pintype "passive"))
      (node (ref "S3") (pin "1") (pinfunction "1_1") (pintype "passive"))
      (node (ref "X4") (pin "6") (pinfunction "KL_6") (pintype "passive"))
    )
    (net (code "21") (name "/MOSI") (class "Default")
      (node (ref "IC8") (pin "15") (pinfunction "PB3(MOSI/OC2)_15") (pintype "bidirectional"))
      (node (ref "JP13") (pin "4") (pinfunction "4_4") (pintype "passive"))
    )
    (net (code "22") (name "/N$29") (class "Default")
      (node (ref "IC8") (pin "19") (pinfunction "ADC6_19") (pintype "bidirectional"))
    )
    (net (code "23") (name "/N$30") (class "Default")
      (node (ref "IC8") (pin "22") (pinfunction "ADC7_22") (pintype "bidirectional"))
    )
    (net (code "24") (name "/PB1") (class "Default")
      (node (ref "IC8") (pin "13") (pinfunction "PB1(OC1A)_13") (pintype "bidirectional"))
      (node (ref "R11") (pin "2") (pinfunction "2_2") (pintype "passive"))
    )
    (net (code "25") (name "/PB2") (class "Default")
      (node (ref "IC1") (pin "41") (pinfunction "PB2_41") (pintype "bidirectional"))
    )
    (net (code "26") (name "/PB3") (class "Default")
      (node (ref "IC1") (pin "42") (pinfunction "PB3_42") (pintype "bidirectional"))
    )
    (net (code "27") (name "/PB4{slash}PWM0") (class "Default")
      (node (ref "IC1") (pin "43") (pinfunction "PB4/PWM0_43") (pintype "bidirectional"))
    )
    (net (code "28") (name "/PB5{slash}PWM1") (class "Default")
      (node (ref "IC1") (pin "44") (pinfunction "PB5/PWM1_44") (pintype "bidirectional"))
    )
    (net (code "29") (name "/PC0") (class "Default")
      (node (ref "IC8") (pin "23") (pinfunction "PC0(ADC0)_23") (pintype "bidirectional"))
      (node (ref "JP4") (pin "2") (pinfunction "2_2") (pintype "passive"))
      (node (ref "X5") (pin "6") (pinfunction "KL_6") (pintype "passive"))
    )
    (net (code "30") (name "/PC1") (class "Default")
      (node (ref "IC8") (pin "24") (pinfunction "PC1(ADC1)_24") (pintype "bidirectional"))
      (node (ref "JP9") (pin "2") (pinfunction "2_2") (pintype "passive"))
      (node (ref "X4") (pin "1") (pinfunction "KL_1") (pintype "passive"))
    )
    (net (code "31") (name "/PC2") (class "Default")
      (node (ref "IC8") (pin "25") (pinfunction "PC2(ADC2)_25") (pintype "bidirectional"))
      (node (ref "JP10") (pin "2") (pinfunction "2_2") (pintype "passive"))
      (node (ref "X4") (pin "2") (pinfunction "KL_2") (pintype "passive"))
    )
    (net (code "32") (name "/PC3") (class "Default")
      (node (ref "IC8") (pin "26") (pinfunction "PC3(ADC3)_26") (pintype "bidirectional"))
      (node (ref "JP11") (pin "2") (pinfunction "2_2") (pintype "passive"))
      (node (ref "X4") (pin "5") (pinfunction "KL_5") (pintype "passive"))
    )
    (net (code "33") (name "/PD2") (class "Default")
      (node (ref "IC8") (pin "32") (pinfunction "PD2(INT0)_32") (pintype "bidirectional"))
      (node (ref "JP8") (pin "2") (pinfunction "2_2") (pintype "passive"))
      (node (ref "X3") (pin "6") (pinfunction "KL_6") (pintype "passive"))
    )
    (net (code "34") (name "/PD3") (class "Default")
      (node (ref "IC8") (pin "1") (pinfunction "PD3(INT1)_1") (pintype "bidirectional"))
      (node (ref "JP7") (pin "2") (pinfunction "2_2") (pintype "passive"))
      (node (ref "X3") (pin "5") (pinfunction "KL_5") (pintype "passive"))
    )
    (net (code "35") (name "/PD4") (class "Default")
      (node (ref "IC8") (pin "2") (pinfunction "PD4(XCK/T0)_2") (pintype "bidirectional"))
      (node (ref "JP5") (pin "2") (pinfunction "2_2") (pintype "passive"))
      (node (ref "X3") (pin "4") (pinfunction "KL_4") (pintype "passive"))
    )
    (net (code "36") (name "/PD5") (class "Default")
      (node (ref "IC8") (pin "9") (pinfunction "PD5(T1)_9") (pintype "bidirectional"))
      (node (ref "JP1") (pin "2") (pinfunction "2_2") (pintype "passive"))
      (node (ref "X5") (pin "1") (pinfunction "KL_1") (pintype "passive"))
    )
    (net (code "37") (name "/PD6") (class "Default")
      (node (ref "IC8") (pin "10") (pinfunction "PD6(AIN0)_10") (pintype "bidirectional"))
      (node (ref "JP2") (pin "2") (pinfunction "2_2") (pintype "passive"))
      (node (ref "X5") (pin "2") (pinfunction "KL_2") (pintype "passive"))
    )
    (net (code "38") (name "/PD7") (class "Default")
      (node (ref "IC8") (pin "11") (pinfunction "PD7(AIN1)_11") (pintype "bidirectional"))
      (node (ref "S4") (pin "1") (pinfunction "1_1") (pintype "passive"))
    )
    (net (code "39") (name "/RESET") (class "Default")
      (node (ref "IC8") (pin "29") (pinfunction "PC6(/RESET)_29") (pintype "bidirectional"))
      (node (ref "JP13") (pin "5") (pinfunction "5_5") (pintype "passive"))
      (node (ref "R37") (pin "2") (pinfunction "2_2") (pintype "passive"))
    )
    (net (code "40") (name "/SCK") (class "Default")
      (node (ref "IC8") (pin "17") (pinfunction "PB5(SCK)_17") (pintype "bidirectional"))
      (node (ref "JP13") (pin "3") (pinfunction "3_3") (pintype "passive"))
      (node (ref "JP6") (pin "2") (pinfunction "2_2") (pintype "passive"))
      (node (ref "X3") (pin "3") (pinfunction "KL_3") (pintype "passive"))
    )
    (net (code "41") (name "/SCL") (class "Default")
      (node (ref "IC8") (pin "28") (pinfunction "PC5(ADC5/SCL)_28") (pintype "bidirectional"))
      (node (ref "J2") (pin "2") (pinfunction "2_2") (pintype "passive"))
    )
    (net (code "42") (name "/SDA") (class "Default")
      (node (ref "IC8") (pin "27") (pinfunction "PC4(ADC4/SDA)_27") (pintype "bidirectional"))
      (node (ref "J2") (pin "1") (pinfunction "1_1") (pintype "passive"))
    )
    (net (code "43") (name "/SDC0{slash}CLK") (class "Default")
      (node (ref "IC1") (pin "105") (pinfunction "PF2/SDC0/CLK_105") (pintype "bidirectional"))
      (node (ref "J3") (pin "5") (pinfunction "CLK(SCLK)_5") (pintype "bidirectional"))
      (node (ref "R5") (pin "1") (pinfunction "1_1") (pintype "passive"))
    )
    (net (code "44") (name "/SDC0{slash}CMD") (class "Default")
      (node (ref "IC1") (pin "103") (pinfunction "PF3/SDC0/CMD_103") (pintype "bidirectional"))
      (node (ref "J3") (pin "3") (pinfunction "CMD(DI)_3") (pintype "bidirectional"))
      (node (ref "R3") (pin "1") (pinfunction "1_1") (pintype "passive"))
    )
    (net (code "45") (name "/SDC0{slash}D0") (class "Default")
      (node (ref "IC1") (pin "106") (pinfunction "PF1/SDC0/D0_106") (pintype "bidirectional"))
      (node (ref "J3") (pin "7") (pinfunction "DAT0(DO)_7") (pintype "bidirectional"))
      (node (ref "R6") (pin "1") (pinfunction "1_1") (pintype "passive"))
    )
    (net (code "46") (name "/SDC0{slash}D1") (class "Default")
      (node (ref "IC1") (pin "107") (pinfunction "PF0/SDC0/D1_107") (pintype "bidirectional"))
      (node (ref "J3") (pin "8") (pinfunction "DAT1_8") (pintype "bidirectional"))
      (node (ref "R4") (pin "1") (pinfunction "1_1") (pintype "passive"))
    )
    (net (code "47") (name "/SDC0{slash}D2") (class "Default")
      (node (ref "IC1") (pin "101") (pinfunction "PF5/SDC0/D2_101") (pintype "bidirectional"))
      (node (ref "J3") (pin "1") (pinfunction "DAT2_1") (pintype "bidirectional"))
      (node (ref "R1") (pin "1") (pinfunction "1_1") (pintype "passive"))
    )
    (net (code "48") (name "/SDC0{slash}D3") (class "Default")
      (node (ref "IC1") (pin "102") (pinfunction "PF4/SDC0/D3_102") (pintype "bidirectional"))
      (node (ref "J3") (pin "2") (pinfunction "CD/DAT3(~{CS})_2") (pintype "bidirectional"))
      (node (ref "R2") (pin "1") (pinfunction "1_1") (pintype "passive"))
    )
    (net (code "49") (name "/SPD_LED") (class "Default")
      (node (ref "IC1") (pin "78") (pinfunction "EPHY_SPD_LED_78") (pintype "bidirectional"))
      (node (ref "R25") (pin "1") (pinfunction "1_1") (pintype "passive"))
    )
    (net (code "50") (name "/SVREF") (class "Default")
      (node (ref "C16") (pin "2") (pinfunction "2_2") (pintype "passive"))
      (node (ref "C17") (pin "1") (pinfunction "1_1") (pintype "passive"))
      (node (ref "IC1") (pin "63") (pinfunction "SVREF1_63") (pintype "bidirectional"))
      (node (ref "IC1") (pin "71") (pinfunction "SVREF0_71") (pintype "bidirectional"))
      (node (ref "R29") (pin "2") (pinfunction "2_2") (pintype "passive"))
      (node (ref "R30") (pin "1") (pinfunction "1_1") (pintype "passive"))
    )
    (net (code "51") (name "/UART0{slash}RX") (class "Default")
      (node (ref "IC1") (pin "49") (pinfunction "PB9/I2C1/SDA_49") (pintype "bidirectional"))
      (node (ref "JP14") (pin "1") (pinfunction "1_1") (pintype "passive"))
    )
    (net (code "52") (name "/UART0{slash}TX") (class "Default")
      (node (ref "IC1") (pin "48") (pinfunction "PB8/I2C1/SCL_48") (pintype "bidirectional"))
      (node (ref "JP14") (pin "2") (pinfunction "2_2") (pintype "passive"))
    )
    (net (code "53") (name "/UART2{slash}RX") (class "Default")
      (node (ref "IC1") (pin "39") (pinfunction "PB0/UART2/TX_39") (pintype "bidirectional"))
      (node (ref "IC8") (pin "30") (pinfunction "PD0(RXD)_30") (pintype "bidirectional"))
    )
    (net (code "54") (name "/UART2{slash}TX") (class "Default")
      (node (ref "IC1") (pin "40") (pinfunction "PB1/UART2/RX_40") (pintype "bidirectional"))
      (node (ref "IC8") (pin "31") (pinfunction "PD1(TXD)_31") (pintype "bidirectional"))
    )
    (net (code "55") (name "/USB_DM") (class "Default")
      (node (ref "IC1") (pin "110") (pinfunction "USB-DM_110") (pintype "bidirectional"))
      (node (ref "X2") (pin "D-") (pinfunction "D-_D-") (pintype "bidirectional"))
    )
    (net (code "56") (name "/USB_DP") (class "Default")
      (node (ref "IC1") (pin "111") (pinfunction "USB-DP_111") (pintype "bidirectional"))
      (node (ref "X2") (pin "D+") (pinfunction "D+_D+") (pintype "bidirectional"))
    )
    (net (code "57") (name "/VRA1") (class "Default")
      (node (ref "C21") (pin "1") (pinfunction "1_1") (pintype "passive"))
      (node (ref "IC1") (pin "117") (pinfunction "VRA1_117") (pintype "bidirectional"))
    )
    (net (code "58") (name "/VRA2") (class "Default")
      (node (ref "C20") (pin "1") (pinfunction "1_1") (pintype "passive"))
      (node (ref "IC1") (pin "118") (pinfunction "VRA2_118") (pintype "bidirectional"))
      (node (ref "R31") (pin "1") (pinfunction "1_1") (pintype "passive"))
    )
    (net (code "59") (name "GND") (class "Default")
      (node (ref "C1") (pin "-") (pinfunction "-_-") (pintype "passive"))
      (node (ref "C10") (pin "2") (pinfunction "2_2") (pintype "passive"))
      (node (ref "C11") (pin "2") (pinfunction "2_2") (pintype "passive"))
      (node (ref "C13") (pin "2") (pinfunction "2_2") (pintype "passive"))
      (node (ref "C14") (pin "2") (pinfunction "2_2") (pintype "passive"))
      (node (ref "C15") (pin "2") (pinfunction "2_2") (pintype "passive"))
      (node (ref "C17") (pin "2") (pinfunction "2_2") (pintype "passive"))
      (node (ref "C18") (pin "2") (pinfunction "2_2") (pintype "passive"))
      (node (ref "C19") (pin "2") (pinfunction "2_2") (pintype "passive"))
      (node (ref "C2") (pin "-") (pinfunction "-_-") (pintype "passive"))
      (node (ref "C20") (pin "2") (pinfunction "2_2") (pintype "passive"))
      (node (ref "C21") (pin "2") (pinfunction "2_2") (pintype "passive"))
      (node (ref "C22") (pin "1") (pinfunction "1_1") (pintype "passive"))
      (node (ref "C23") (pin "1") (pinfunction "1_1") (pintype "passive"))
      (node (ref "C24") (pin "2") (pinfunction "2_2") (pintype "passive"))
      (node (ref "C25") (pin "2") (pinfunction "2_2") (pintype "passive"))
      (node (ref "C26") (pin "2") (pinfunction "2_2") (pintype "passive"))
      (node (ref "C27") (pin "2") (pinfunction "2_2") (pintype "passive"))
      (node (ref "C28") (pin "2") (pinfunction "2_2") (pintype "passive"))
      (node (ref "C29") (pin "2") (pinfunction "2_2") (pintype "passive"))
      (node (ref "C3") (pin "2") (pinfunction "2_2") (pintype "passive"))
      (node (ref "C30") (pin "2") (pinfunction "2_2") (pintype "passive"))
      (node (ref "C31") (pin "2") (pinfunction "2_2") (pintype "passive"))
      (node (ref "C32") (pin "2") (pinfunction "2_2") (pintype "passive"))
      (node (ref "C33") (pin "2") (pinfunction "2_2") (pintype "passive"))
      (node (ref "C34") (pin "2") (pinfunction "2_2") (pintype "passive"))
      (node (ref "C35") (pin "2") (pinfunction "2_2") (pintype "passive"))
      (node (ref "C36") (pin "2") (pinfunction "2_2") (pintype "passive"))
      (node (ref "C37") (pin "2") (pinfunction "2_2") (pintype "passive"))
      (node (ref "C4") (pin "2") (pinfunction "2_2") (pintype "passive"))
      (node (ref "C40") (pin "1") (pinfunction "1_1") (pintype "passive"))
      (node (ref "C41") (pin "2") (pinfunction "2_2") (pintype "passive"))
      (node (ref "C42") (pin "2") (pinfunction "2_2") (pintype "passive"))
      (node (ref "C43") (pin "2") (pinfunction "2_2") (pintype "passive"))
      (node (ref "C44") (pin "2") (pinfunction "2_2") (pintype "passive"))
      (node (ref "C46") (pin "1") (pinfunction "1_1") (pintype "passive"))
      (node (ref "C47") (pin "1") (pinfunction "1_1") (pintype "passive"))
      (node (ref "C48") (pin "1") (pinfunction "1_1") (pintype "passive"))
      (node (ref "C5") (pin "2") (pinfunction "2_2") (pintype "passive"))
      (node (ref "C6") (pin "2") (pinfunction "2_2") (pintype "passive"))
      (node (ref "C7") (pin "2") (pinfunction "2_2") (pintype "passive"))
      (node (ref "C8") (pin "2") (pinfunction "2_2") (pintype "passive"))
      (node (ref "C9") (pin "2") (pinfunction "2_2") (pintype "passive"))
      (node (ref "H1") (pin "B2,8") (pinfunction "MOUNT_B2,8") (pintype "passive"))
      (node (ref "H2") (pin "B2,8") (pinfunction "MOUNT_B2,8") (pintype "passive"))
      (node (ref "H3") (pin "B2,8") (pinfunction "MOUNT_B2,8") (pintype "passive"))
      (node (ref "H4") (pin "B2,8") (pinfunction "MOUNT_B2,8") (pintype "passive"))
      (node (ref "IC1") (pin "116") (pinfunction "AGND_116") (pintype "bidirectional"))
      (node (ref "IC1") (pin "P$2") (pinfunction "PAD_P$2") (pintype "bidirectional"))
      (node (ref "IC4") (pin "1") (pinfunction "GND_1") (pintype "input"))
      (node (ref "IC5") (pin "1") (pinfunction "GND_1") (pintype "input"))
      (node (ref "IC6") (pin "1") (pinfunction "GND_1") (pintype "input"))
      (node (ref "IC7") (pin "1") (pinfunction "GND_1") (pintype "input"))
      (node (ref "IC8") (pin "21") (pinfunction "AGND_21") (pintype "bidirectional"))
      (node (ref "IC8") (pin "3") (pinfunction "GND_3") (pintype "bidirectional"))
      (node (ref "IC8") (pin "5") (pinfunction "GND_5") (pintype "bidirectional"))
      (node (ref "J1") (pin "1") (pinfunction "15_1") (pintype "passive"))
      (node (ref "J1") (pin "10") (pinfunction "6_10") (pintype "passive"))
      (node (ref "J1") (pin "4") (pinfunction "12_4") (pintype "passive"))
      (node (ref "J1") (pin "7") (pinfunction "9_7") (pintype "passive"))
      (node (ref "J2") (pin "4") (pinfunction "4_4") (pintype "passive"))
      (node (ref "J3") (pin "6") (pinfunction "GND_6") (pintype "power_in"))
      (node (ref "J3") (pin "S1") (pinfunction "S_S1") (pintype "passive"))
      (node (ref "J3") (pin "S2") (pinfunction "S_S2") (pintype "passive"))
      (node (ref "J3") (pin "S3") (pinfunction "S_S3") (pintype "passive"))
      (node (ref "J3") (pin "S4") (pinfunction "S_S4") (pintype "passive"))
      (node (ref "JP13") (pin "6") (pinfunction "6_6") (pintype "passive"))
      (node (ref "JP14") (pin "3") (pinfunction "3_3") (pintype "passive"))
      (node (ref "LD1") (pin "C") (pinfunction "C_C") (pintype "passive"))
      (node (ref "LD2") (pin "C") (pinfunction "C_C") (pintype "passive"))
      (node (ref "M1") (pin "P$1") (pinfunction "VIN-_P$1") (pintype "input"))
      (node (ref "M1") (pin "P$4") (pinfunction "VOUT-_P$4") (pintype "output"))
      (node (ref "R10") (pin "2") (pinfunction "2_2") (pintype "passive"))
      (node (ref "R27") (pin "2") (pinfunction "2_2") (pintype "passive"))
      (node (ref "R28") (pin "1") (pinfunction "1_1") (pintype "passive"))
      (node (ref "R29") (pin "1") (pinfunction "1_1") (pintype "passive"))
      (node (ref "R31") (pin "2") (pinfunction "2_2") (pintype "passive"))
      (node (ref "R33") (pin "1") (pinfunction "1_1") (pintype "passive"))
      (node (ref "R38") (pin "1") (pinfunction "1_1") (pintype "passive"))
      (node (ref "R40") (pin "1") (pinfunction "1_1") (pintype "passive"))
      (node (ref "R42") (pin "1") (pinfunction "1_1") (pintype "passive"))
      (node (ref "R44") (pin "1") (pinfunction "1_1") (pintype "passive"))
      (node (ref "R46") (pin "1") (pinfunction "1_1") (pintype "passive"))
      (node (ref "R48") (pin "1") (pinfunction "1_1") (pintype "passive"))
      (node (ref "R50") (pin "1") (pinfunction "1_1") (pintype "passive"))
      (node (ref "R52") (pin "1") (pinfunction "1_1") (pintype "passive"))
      (node (ref "R54") (pin "1") (pinfunction "1_1") (pintype "passive"))
      (node (ref "R56") (pin "1") (pinfunction "1_1") (pintype "passive"))
      (node (ref "R9") (pin "1") (pinfunction "1_1") (pintype "passive"))
      (node (ref "S3") (pin "2") (pinfunction "2_2") (pintype "passive"))
      (node (ref "S4") (pin "2") (pinfunction "2_2") (pintype "passive"))
      (node (ref "SJ6") (pin "3") (pinfunction "3_3") (pintype "passive"))
      (node (ref "SJ7") (pin "1") (pinfunction "1_1") (pintype "passive"))
      (node (ref "SJ8") (pin "3") (pinfunction "3_3") (pintype "passive"))
      (node (ref "U$3") (pin "G-") (pinfunction "G-_G-") (pintype "bidirectional"))
      (node (ref "U$3") (pin "GND") (pinfunction "GND_GND") (pintype "bidirectional"))
      (node (ref "U$3") (pin "SHIELD1") (pinfunction "SHIELD0_SHIELD1") (pintype "bidirectional"))
      (node (ref "U$3") (pin "SHIELD2") (pinfunction "SHIELD1_SHIELD2") (pintype "bidirectional"))
      (node (ref "U$3") (pin "Y-") (pinfunction "Y-_Y-") (pintype "bidirectional"))
      (node (ref "X1") (pin "2") (pinfunction "KL_2") (pintype "passive"))
      (node (ref "X2") (pin "GND") (pinfunction "GND_GND") (pintype "bidirectional"))
      (node (ref "X3") (pin "1") (pinfunction "KL_1") (pintype "passive"))
      (node (ref "X4") (pin "3") (pinfunction "KL_3") (pintype "passive"))
      (node (ref "X5") (pin "3") (pinfunction "KL_3") (pintype "passive"))
    )
    (net (code "60") (name "Net-(C13-Pad1)") (class "Default")
      (node (ref "C13") (pin "1") (pinfunction "1_1") (pintype "passive"))
      (node (ref "L2") (pin "2") (pinfunction "2_2") (pintype "passive"))
      (node (ref "R20") (pin "2") (pinfunction "2_2") (pintype "passive"))
      (node (ref "R21") (pin "2") (pinfunction "2_2") (pintype "passive"))
      (node (ref "U$3") (pin "P4") (pinfunction "P4_P4") (pintype "bidirectional"))
    )
    (net (code "61") (name "Net-(C14-Pad1)") (class "Default")
      (node (ref "C14") (pin "1") (pinfunction "1_1") (pintype "passive"))
      (node (ref "R22") (pin "2") (pinfunction "2_2") (pintype "passive"))
      (node (ref "R23") (pin "2") (pinfunction "2_2") (pintype "passive"))
      (node (ref "U$3") (pin "P5") (pinfunction "P5_P5") (pintype "bidirectional"))
    )
    (net (code "62") (name "Net-(IC1-EPHY_RTX)") (class "Default")
      (node (ref "IC1") (pin "94") (pinfunction "EPHY_RTX_94") (pintype "bidirectional"))
      (node (ref "R27") (pin "1") (pinfunction "1_1") (pintype "passive"))
    )
    (net (code "63") (name "Net-(IC1-LRADC0)") (class "Default")
      (node (ref "C22") (pin "2") (pinfunction "2_2") (pintype "passive"))
      (node (ref "IC1") (pin "112") (pinfunction "LRADC0_112") (pintype "bidirectional"))
      (node (ref "R32") (pin "1") (pinfunction "1_1") (pintype "passive"))
    )
    (net (code "64") (name "Net-(IC1-PF6)") (class "Default")
      (node (ref "IC1") (pin "100") (pinfunction "PF6_100") (pintype "bidirectional"))
      (node (ref "SJ8") (pin "2") (pinfunction "2_2") (pintype "passive"))
    )
    (net (code "65") (name "Net-(IC1-RESET)") (class "Default")
      (node (ref "C15") (pin "1") (pinfunction "1_1") (pintype "passive"))
      (node (ref "IC1") (pin "99") (pinfunction "RESET_99") (pintype "bidirectional"))
      (node (ref "R26") (pin "1") (pinfunction "1_1") (pintype "passive"))
    )
    (net (code "66") (name "Net-(IC1-RTC-VIO)") (class "Default")
      (node (ref "C23") (pin "2") (pinfunction "2_2") (pintype "passive"))
      (node (ref "IC1") (pin "97") (pinfunction "RTC-VIO_97") (pintype "bidirectional"))
    )
    (net (code "67") (name "Net-(IC1-SZQ)") (class "Default")
      (node (ref "IC1") (pin "73") (pinfunction "SZQ_73") (pintype "bidirectional"))
      (node (ref "R28") (pin "2") (pinfunction "2_2") (pintype "passive"))
    )
    (net (code "68") (name "Net-(IC1-X24MIN)") (class "Default")
      (node (ref "C46") (pin "2") (pinfunction "2_2") (pintype "passive"))
      (node (ref "IC1") (pin "75") (pinfunction "X24MIN_75") (pintype "bidirectional"))
      (node (ref "Q1") (pin "2") (pinfunction "2_2") (pintype "passive"))
    )
    (net (code "69") (name "Net-(IC1-X24MOUNT)") (class "Default")
      (node (ref "C40") (pin "2") (pinfunction "2_2") (pintype "passive"))
      (node (ref "IC1") (pin "74") (pinfunction "X24MOUNT_74") (pintype "bidirectional"))
      (node (ref "Q1") (pin "1") (pinfunction "1_1") (pintype "passive"))
    )
    (net (code "70") (name "Net-(IC1-X32KIN)") (class "Default")
      (node (ref "C47") (pin "2") (pinfunction "2_2") (pintype "passive"))
      (node (ref "IC1") (pin "96") (pinfunction "X32KIN_96") (pintype "bidirectional"))
      (node (ref "Q2") (pin "1") (pinfunction "1_1") (pintype "passive"))
    )
    (net (code "71") (name "Net-(IC1-X32KOUT)") (class "Default")
      (node (ref "C48") (pin "2") (pinfunction "2_2") (pintype "passive"))
      (node (ref "IC1") (pin "95") (pinfunction "X32KOUT_95") (pintype "bidirectional"))
      (node (ref "Q2") (pin "2") (pinfunction "2_2") (pintype "passive"))
    )
    (net (code "72") (name "Net-(IC4-OUT)") (class "Default")
      (node (ref "C4") (pin "1") (pinfunction "1_1") (pintype "passive"))
      (node (ref "IC4") (pin "2") (pinfunction "OUT_2") (pintype "passive"))
      (node (ref "SJ2") (pin "1") (pinfunction "1_1") (pintype "passive"))
    )
    (net (code "73") (name "Net-(IC5-OUT)") (class "Default")
      (node (ref "C6") (pin "1") (pinfunction "1_1") (pintype "passive"))
      (node (ref "IC5") (pin "2") (pinfunction "OUT_2") (pintype "passive"))
      (node (ref "SJ3") (pin "1") (pinfunction "1_1") (pintype "passive"))
    )
    (net (code "74") (name "Net-(IC6-OUT)") (class "Default")
      (node (ref "C8") (pin "1") (pinfunction "1_1") (pintype "passive"))
      (node (ref "IC6") (pin "2") (pinfunction "OUT_2") (pintype "passive"))
      (node (ref "SJ4") (pin "1") (pinfunction "1_1") (pintype "passive"))
    )
    (net (code "75") (name "Net-(IC7-OUT)") (class "Default")
      (node (ref "C10") (pin "1") (pinfunction "1_1") (pintype "passive"))
      (node (ref "IC7") (pin "2") (pinfunction "OUT_2") (pintype "passive"))
      (node (ref "SJ5") (pin "1") (pinfunction "1_1") (pintype "passive"))
    )
    (net (code "76") (name "Net-(IC8-PB0(ICP))") (class "Default")
      (node (ref "IC8") (pin "12") (pinfunction "PB0(ICP)_12") (pintype "bidirectional"))
      (node (ref "R12") (pin "2") (pinfunction "2_2") (pintype "passive"))
    )
    (net (code "77") (name "Net-(J1-4)") (class "Default")
      (node (ref "J1") (pin "12") (pinfunction "4_12") (pintype "passive"))
      (node (ref "SJ7") (pin "2") (pinfunction "2_2") (pintype "passive"))
    )
    (net (code "78") (name "Net-(J1-5)") (class "Default")
      (node (ref "J1") (pin "11") (pinfunction "5_11") (pintype "passive"))
      (node (ref "SJ6") (pin "2") (pinfunction "2_2") (pintype "passive"))
    )
    (net (code "79") (name "Net-(JP1-Pad1)") (class "Default")
      (node (ref "JP1") (pin "1") (pinfunction "1_1") (pintype "passive"))
      (node (ref "R34") (pin "1") (pinfunction "1_1") (pintype "passive"))
    )
    (net (code "80") (name "Net-(JP1-Pad3)") (class "Default")
      (node (ref "JP1") (pin "3") (pinfunction "3_3") (pintype "passive"))
      (node (ref "R9") (pin "2") (pinfunction "2_2") (pintype "passive"))
    )
    (net (code "81") (name "Net-(JP2-Pad1)") (class "Default")
      (node (ref "JP2") (pin "1") (pinfunction "1_1") (pintype "passive"))
      (node (ref "R35") (pin "1") (pinfunction "1_1") (pintype "passive"))
    )
    (net (code "82") (name "Net-(JP2-Pad3)") (class "Default")
      (node (ref "JP2") (pin "3") (pinfunction "3_3") (pintype "passive"))
      (node (ref "R33") (pin "2") (pinfunction "2_2") (pintype "passive"))
    )
    (net (code "83") (name "Net-(JP3-Pad1)") (class "Default")
      (node (ref "JP3") (pin "1") (pinfunction "1_1") (pintype "passive"))
      (node (ref "R39") (pin "1") (pinfunction "1_1") (pintype "passive"))
    )
    (net (code "84") (name "Net-(JP3-Pad3)") (class "Default")
      (node (ref "JP3") (pin "3") (pinfunction "3_3") (pintype "passive"))
      (node (ref "R38") (pin "2") (pinfunction "2_2") (pintype "passive"))
    )
    (net (code "85") (name "Net-(JP4-Pad1)") (class "Default")
      (node (ref "JP4") (pin "1") (pinfunction "1_1") (pintype "passive"))
      (node (ref "R41") (pin "1") (pinfunction "1_1") (pintype "passive"))
    )
    (net (code "86") (name "Net-(JP4-Pad3)") (class "Default")
      (node (ref "JP4") (pin "3") (pinfunction "3_3") (pintype "passive"))
      (node (ref "R40") (pin "2") (pinfunction "2_2") (pintype "passive"))
    )
    (net (code "87") (name "Net-(JP5-Pad1)") (class "Default")
      (node (ref "JP5") (pin "1") (pinfunction "1_1") (pintype "passive"))
      (node (ref "R43") (pin "1") (pinfunction "1_1") (pintype "passive"))
    )
    (net (code "88") (name "Net-(JP5-Pad3)") (class "Default")
      (node (ref "JP5") (pin "3") (pinfunction "3_3") (pintype "passive"))
      (node (ref "R42") (pin "2") (pinfunction "2_2") (pintype "passive"))
    )
    (net (code "89") (name "Net-(JP6-Pad1)") (class "Default")
      (node (ref "JP6") (pin "1") (pinfunction "1_1") (pintype "passive"))
      (node (ref "R45") (pin "1") (pinfunction "1_1") (pintype "passive"))
    )
    (net (code "90") (name "Net-(JP6-Pad3)") (class "Default")
      (node (ref "JP6") (pin "3") (pinfunction "3_3") (pintype "passive"))
      (node (ref "R44") (pin "2") (pinfunction "2_2") (pintype "passive"))
    )
    (net (code "91") (name "Net-(JP7-Pad1)") (class "Default")
      (node (ref "JP7") (pin "1") (pinfunction "1_1") (pintype "passive"))
      (node (ref "R47") (pin "1") (pinfunction "1_1") (pintype "passive"))
    )
    (net (code "92") (name "Net-(JP7-Pad3)") (class "Default")
      (node (ref "JP7") (pin "3") (pinfunction "3_3") (pintype "passive"))
      (node (ref "R46") (pin "2") (pinfunction "2_2") (pintype "passive"))
    )
    (net (code "93") (name "Net-(JP8-Pad1)") (class "Default")
      (node (ref "JP8") (pin "1") (pinfunction "1_1") (pintype "passive"))
      (node (ref "R49") (pin "1") (pinfunction "1_1") (pintype "passive"))
    )
    (net (code "94") (name "Net-(JP8-Pad3)") (class "Default")
      (node (ref "JP8") (pin "3") (pinfunction "3_3") (pintype "passive"))
      (node (ref "R48") (pin "2") (pinfunction "2_2") (pintype "passive"))
    )
    (net (code "95") (name "Net-(JP9-Pad1)") (class "Default")
      (node (ref "JP9") (pin "1") (pinfunction "1_1") (pintype "passive"))
      (node (ref "R51") (pin "1") (pinfunction "1_1") (pintype "passive"))
    )
    (net (code "96") (name "Net-(JP9-Pad3)") (class "Default")
      (node (ref "JP9") (pin "3") (pinfunction "3_3") (pintype "passive"))
      (node (ref "R50") (pin "2") (pinfunction "2_2") (pintype "passive"))
    )
    (net (code "97") (name "Net-(JP10-Pad1)") (class "Default")
      (node (ref "JP10") (pin "1") (pinfunction "1_1") (pintype "passive"))
      (node (ref "R53") (pin "1") (pinfunction "1_1") (pintype "passive"))
    )
    (net (code "98") (name "Net-(JP10-Pad3)") (class "Default")
      (node (ref "JP10") (pin "3") (pinfunction "3_3") (pintype "passive"))
      (node (ref "R52") (pin "2") (pinfunction "2_2") (pintype "passive"))
    )
    (net (code "99") (name "Net-(JP11-Pad1)") (class "Default")
      (node (ref "JP11") (pin "1") (pinfunction "1_1") (pintype "passive"))
      (node (ref "R55") (pin "1") (pinfunction "1_1") (pintype "passive"))
    )
    (net (code "100") (name "Net-(JP11-Pad3)") (class "Default")
      (node (ref "JP11") (pin "3") (pinfunction "3_3") (pintype "passive"))
      (node (ref "R54") (pin "2") (pinfunction "2_2") (pintype "passive"))
    )
    (net (code "101") (name "Net-(JP12-Pad1)") (class "Default")
      (node (ref "JP12") (pin "1") (pinfunction "1_1") (pintype "passive"))
      (node (ref "R57") (pin "1") (pinfunction "1_1") (pintype "passive"))
    )
    (net (code "102") (name "Net-(JP12-Pad3)") (class "Default")
      (node (ref "JP12") (pin "3") (pinfunction "3_3") (pintype "passive"))
      (node (ref "R56") (pin "2") (pinfunction "2_2") (pintype "passive"))
    )
    (net (code "103") (name "Net-(LD1-PadA)") (class "Default")
      (node (ref "LD1") (pin "A") (pinfunction "A_A") (pintype "passive"))
      (node (ref "R12") (pin "1") (pinfunction "1_1") (pintype "passive"))
    )
    (net (code "104") (name "Net-(LD2-PadA)") (class "Default")
      (node (ref "LD2") (pin "A") (pinfunction "A_A") (pintype "passive"))
      (node (ref "R11") (pin "1") (pinfunction "1_1") (pintype "passive"))
    )
    (net (code "105") (name "Net-(LD3-PadC)") (class "Default")
      (node (ref "LD3") (pin "C") (pinfunction "C_C") (pintype "passive"))
      (node (ref "R10") (pin "1") (pinfunction "1_1") (pintype "passive"))
    )
    (net (code "106") (name "Net-(M1-VOUT+)") (class "Default")
      (node (ref "C2") (pin "+") (pinfunction "+_+") (pintype "passive"))
      (node (ref "M1") (pin "P$3") (pinfunction "VOUT+_P$3") (pintype "output"))
      (node (ref "SJ1") (pin "1") (pinfunction "1_1") (pintype "passive"))
    )
    (net (code "107") (name "Net-(R24-Pad2)") (class "Default")
      (node (ref "R24") (pin "2") (pinfunction "2_2") (pintype "passive"))
      (node (ref "U$3") (pin "G+") (pinfunction "G+_G+") (pintype "bidirectional"))
    )
    (net (code "108") (name "Net-(R25-Pad2)") (class "Default")
      (node (ref "R25") (pin "2") (pinfunction "2_2") (pintype "passive"))
      (node (ref "U$3") (pin "Y+") (pinfunction "Y+_Y+") (pintype "bidirectional"))
    )
    (net (code "109") (name "Net-(R36-Pad2)") (class "Default")
      (node (ref "R36") (pin "2") (pinfunction "2_2") (pintype "passive"))
      (node (ref "SJ8") (pin "1") (pinfunction "1_1") (pintype "passive"))
    )
    (net (code "110") (name "Net-(X1A-KL)") (class "Default")
      (node (ref "D1") (pin "A") (pinfunction "A_A") (pintype "passive"))
      (node (ref "X1") (pin "1") (pinfunction "KL_1") (pintype "passive"))
    )
    (net (code "111") (name "VDD") (class "Default")
      (node (ref "C1") (pin "+") (pinfunction "+_+") (pintype "passive"))
      (node (ref "D1") (pin "C") (pinfunction "C_C") (pintype "passive"))
      (node (ref "M1") (pin "P$2") (pinfunction "VIN+_P$2") (pintype "input"))
    )
    (net (code "112") (name "unconnected-(IC1-HBIAS-Pad119)") (class "Default")
      (node (ref "IC1") (pin "119") (pinfunction "HBIAS_119") (pintype "bidirectional"))
    )
    (net (code "113") (name "unconnected-(IC1-HPCOM-Pad125)") (class "Default")
      (node (ref "IC1") (pin "125") (pinfunction "HPCOM_125") (pintype "bidirectional"))
    )
    (net (code "114") (name "unconnected-(IC1-HPCOMFB-Pad124)") (class "Default")
      (node (ref "IC1") (pin "124") (pinfunction "HPCOMFB_124") (pintype "bidirectional"))
    )
    (net (code "115") (name "unconnected-(IC1-HPOUTL-Pad121)") (class "Default")
      (node (ref "IC1") (pin "121") (pinfunction "HPOUTL_121") (pintype "bidirectional"))
    )
    (net (code "116") (name "unconnected-(IC1-HPOUTR-Pad120)") (class "Default")
      (node (ref "IC1") (pin "120") (pinfunction "HPOUTR_120") (pintype "bidirectional"))
    )
    (net (code "117") (name "unconnected-(IC1-HPVCCBP-Pad123)") (class "Default")
      (node (ref "IC1") (pin "123") (pinfunction "HPVCCBP_123") (pintype "bidirectional"))
    )
    (net (code "118") (name "unconnected-(IC1-MICIN1N-Pad114)") (class "Default")
      (node (ref "IC1") (pin "114") (pinfunction "MICIN1N_114") (pintype "bidirectional"))
    )
    (net (code "119") (name "unconnected-(IC1-MICIN1P-Pad113)") (class "Default")
      (node (ref "IC1") (pin "113") (pinfunction "MICIN1P_113") (pintype "bidirectional"))
    )
    (net (code "120") (name "unconnected-(IC1-PB6{slash}I2C0{slash}SCL-Pad45)") (class "Default")
      (node (ref "IC1") (pin "45") (pinfunction "PB6/I2C0/SCL_45") (pintype "bidirectional"))
    )
    (net (code "121") (name "unconnected-(IC1-PB7{slash}I2C0{slash}SDA-Pad46)") (class "Default")
      (node (ref "IC1") (pin "46") (pinfunction "PB7/I2C0/SDA_46") (pintype "bidirectional"))
    )
    (net (code "122") (name "unconnected-(IC1-PC0{slash}SPI1{slash}MISO-Pad52)") (class "Default")
      (node (ref "IC1") (pin "52") (pinfunction "PC0/SPI1/MISO_52") (pintype "bidirectional"))
    )
    (net (code "123") (name "unconnected-(IC1-PC1{slash}SPI1{slash}SCK-Pad53)") (class "Default")
      (node (ref "IC1") (pin "53") (pinfunction "PC1/SPI1/SCK_53") (pintype "bidirectional"))
    )
    (net (code "124") (name "unconnected-(IC1-PC2{slash}SPI1{slash}CS-Pad54)") (class "Default")
      (node (ref "IC1") (pin "54") (pinfunction "PC2/SPI1/CS_54") (pintype "bidirectional"))
    )
    (net (code "125") (name "unconnected-(IC1-PC3{slash}SPI1{slash}MOSI-Pad55)") (class "Default")
      (node (ref "IC1") (pin "55") (pinfunction "PC3/SPI1/MOSI_55") (pintype "bidirectional"))
    )
    (net (code "126") (name "unconnected-(IC1-PE0{slash}CSI-CLK-{slash}LCD-CLK-Pad37)") (class "Default")
      (node (ref "IC1") (pin "37") (pinfunction "PE0/CSI-CLK-/LCD-CLK_37") (pintype "bidirectional"))
    )
    (net (code "127") (name "unconnected-(IC1-PE1{slash}CSI-MCLK{slash}LCD-DE-Pad36)") (class "Default")
      (node (ref "IC1") (pin "36") (pinfunction "PE1/CSI-MCLK/LCD-DE_36") (pintype "bidirectional"))
    )
    (net (code "128") (name "unconnected-(IC1-PE2{slash}CSI-HSYNC{slash}LCD-HSYNC-Pad35)") (class "Default")
      (node (ref "IC1") (pin "35") (pinfunction "PE2/CSI-HSYNC/LCD-HSYNC_35") (pintype "bidirectional"))
    )
    (net (code "129") (name "unconnected-(IC1-PE3{slash}CSI-VSYNC{slash}LCD-VSYNC-Pad34)") (class "Default")
      (node (ref "IC1") (pin "34") (pinfunction "PE3/CSI-VSYNC/LCD-VSYNC_34") (pintype "bidirectional"))
    )
    (net (code "130") (name "unconnected-(IC1-PE4{slash}CSI-D0{slash}LCD-D2-Pad33)") (class "Default")
      (node (ref "IC1") (pin "33") (pinfunction "PE4/CSI-D0/LCD-D2_33") (pintype "bidirectional"))
    )
    (net (code "131") (name "unconnected-(IC1-PE5{slash}CSI-D1{slash}-LCD-D3-Pad32)") (class "Default")
      (node (ref "IC1") (pin "32") (pinfunction "PE5/CSI-D1/-LCD-D3_32") (pintype "bidirectional"))
    )
    (net (code "132") (name "unconnected-(IC1-PE6{slash}CSI-D2{slash}LCD-D4-Pad31)") (class "Default")
      (node (ref "IC1") (pin "31") (pinfunction "PE6/CSI-D2/LCD-D4_31") (pintype "bidirectional"))
    )
    (net (code "133") (name "unconnected-(IC1-PE7{slash}CSI-D3{slash}LCD-D5-Pad30)") (class "Default")
      (node (ref "IC1") (pin "30") (pinfunction "PE7/CSI-D3/LCD-D5_30") (pintype "bidirectional"))
    )
    (net (code "134") (name "unconnected-(IC1-PE8{slash}CSI-D4{slash}LCD-D6-Pad28)") (class "Default")
      (node (ref "IC1") (pin "28") (pinfunction "PE8/CSI-D4/LCD-D6_28") (pintype "bidirectional"))
    )
    (net (code "135") (name "unconnected-(IC1-PE9{slash}CSI-D5{slash}LCD-D7-Pad27)") (class "Default")
      (node (ref "IC1") (pin "27") (pinfunction "PE9/CSI-D5/LCD-D7_27") (pintype "bidirectional"))
    )
    (net (code "136") (name "unconnected-(IC1-PE10{slash}CSI-D6{slash}LCD-D10-Pad24)") (class "Default")
      (node (ref "IC1") (pin "24") (pinfunction "PE10/CSI-D6/LCD-D10_24") (pintype "bidirectional"))
    )
    (net (code "137") (name "unconnected-(IC1-PE11{slash}CSI-D7{slash}LCD-D11-Pad23)") (class "Default")
      (node (ref "IC1") (pin "23") (pinfunction "PE11/CSI-D7/LCD-D11_23") (pintype "bidirectional"))
    )
    (net (code "138") (name "unconnected-(IC1-PE12{slash}CSI-D8{slash}LCD-D12-Pad22)") (class "Default")
      (node (ref "IC1") (pin "22") (pinfunction "PE12/CSI-D8/LCD-D12_22") (pintype "bidirectional"))
    )
    (net (code "139") (name "unconnected-(IC1-PE13{slash}CSI-D9{slash}LCD-D13-Pad18)") (class "Default")
      (node (ref "IC1") (pin "18") (pinfunction "PE13/CSI-D9/LCD-D13_18") (pintype "bidirectional"))
    )
    (net (code "140") (name "unconnected-(IC1-PE14{slash}CSI-D10{slash}LCD-D14-Pad17)") (class "Default")
      (node (ref "IC1") (pin "17") (pinfunction "PE14/CSI-D10/LCD-D14_17") (pintype "bidirectional"))
    )
    (net (code "141") (name "unconnected-(IC1-PE15{slash}CSI-D11{slash}LCD-D15-Pad16)") (class "Default")
      (node (ref "IC1") (pin "16") (pinfunction "PE15/CSI-D11/LCD-D15_16") (pintype "bidirectional"))
    )
    (net (code "142") (name "unconnected-(IC1-PE16{slash}CSI-D12{slash}LCD-D18-Pad15)") (class "Default")
      (node (ref "IC1") (pin "15") (pinfunction "PE16/CSI-D12/LCD-D18_15") (pintype "bidirectional"))
    )
    (net (code "143") (name "unconnected-(IC1-PE17{slash}CSI-D13{slash}LCD-D19-Pad14)") (class "Default")
      (node (ref "IC1") (pin "14") (pinfunction "PE17/CSI-D13/LCD-D19_14") (pintype "bidirectional"))
    )
    (net (code "144") (name "unconnected-(IC1-PE18{slash}CSI-D14{slash}LCD-D20-Pad13)") (class "Default")
      (node (ref "IC1") (pin "13") (pinfunction "PE18/CSI-D14/LCD-D20_13") (pintype "bidirectional"))
    )
    (net (code "145") (name "unconnected-(IC1-PE19{slash}CSI-D15{slash}LCD-D21-Pad11)") (class "Default")
      (node (ref "IC1") (pin "11") (pinfunction "PE19/CSI-D15/LCD-D21_11") (pintype "bidirectional"))
    )
    (net (code "146") (name "unconnected-(IC1-PE20{slash}CSI-FIELD{slash}CSI-MIPI-M-CLK-Pad10)") (class "Default")
      (node (ref "IC1") (pin "10") (pinfunction "PE20/CSI-FIELD/CSI-MIPI-M-CLK_10") (pintype "bidirectional"))
    )
    (net (code "147") (name "unconnected-(IC1-PE23{slash}LCD-D22{slash}-Pad7)") (class "Default")
      (node (ref "IC1") (pin "7") (pinfunction "PE23/LCD-D22/_7") (pintype "bidirectional"))
    )
    (net (code "148") (name "unconnected-(IC1-PE24{slash}LCD-D23-Pad6)") (class "Default")
      (node (ref "IC1") (pin "6") (pinfunction "PE24/LCD-D23_6") (pintype "bidirectional"))
    )
    (net (code "149") (name "unconnected-(IC1-PG0{slash}SDC1{slash}CLK-Pad5)") (class "Default")
      (node (ref "IC1") (pin "5") (pinfunction "PG0/SDC1/CLK_5") (pintype "bidirectional"))
    )
    (net (code "150") (name "unconnected-(IC1-PG1{slash}SDC1{slash}CMD-Pad4)") (class "Default")
      (node (ref "IC1") (pin "4") (pinfunction "PG1/SDC1/CMD_4") (pintype "bidirectional"))
    )
    (net (code "151") (name "unconnected-(IC1-PG2{slash}SDC1{slash}D0-Pad3)") (class "Default")
      (node (ref "IC1") (pin "3") (pinfunction "PG2/SDC1/D0_3") (pintype "bidirectional"))
    )
    (net (code "152") (name "unconnected-(IC1-PG3{slash}SDC1{slash}D1-Pad2)") (class "Default")
      (node (ref "IC1") (pin "2") (pinfunction "PG3/SDC1/D1_2") (pintype "bidirectional"))
    )
    (net (code "153") (name "unconnected-(IC1-PG4{slash}SDC1{slash}D2-Pad1)") (class "Default")
      (node (ref "IC1") (pin "1") (pinfunction "PG4/SDC1/D2_1") (pintype "bidirectional"))
    )
    (net (code "154") (name "unconnected-(IC1-PG5{slash}SDC1{slash}D3-Pad128)") (class "Default")
      (node (ref "IC1") (pin "128") (pinfunction "PG5/SDC1/D3_128") (pintype "bidirectional"))
    )
    (net (code "155") (name "unconnected-(IC8-AREF-Pad20)") (class "Default")
      (node (ref "IC8") (pin "20") (pinfunction "AREF_20") (pintype "bidirectional"))
    )
    (net (code "156") (name "unconnected-(IC8-PB6(XTAL1{slash}TOSC1)-Pad7)") (class "Default")
      (node (ref "IC8") (pin "7") (pinfunction "PB6(XTAL1/TOSC1)_7") (pintype "bidirectional"))
    )
    (net (code "157") (name "unconnected-(IC8-PB7(XTAL2{slash}TOSC2)-Pad8)") (class "Default")
      (node (ref "IC8") (pin "8") (pinfunction "PB7(XTAL2/TOSC2)_8") (pintype "bidirectional"))
    )
    (net (code "158") (name "unconnected-(U$3-PadNC)") (class "Default")
      (node (ref "U$3") (pin "NC") (pinfunction "NC_NC") (pintype "bidirectional"))
    )
  )
)
